# mote_cc3200v8.net
KiCad netlist of a schematic drawn in EAGLE
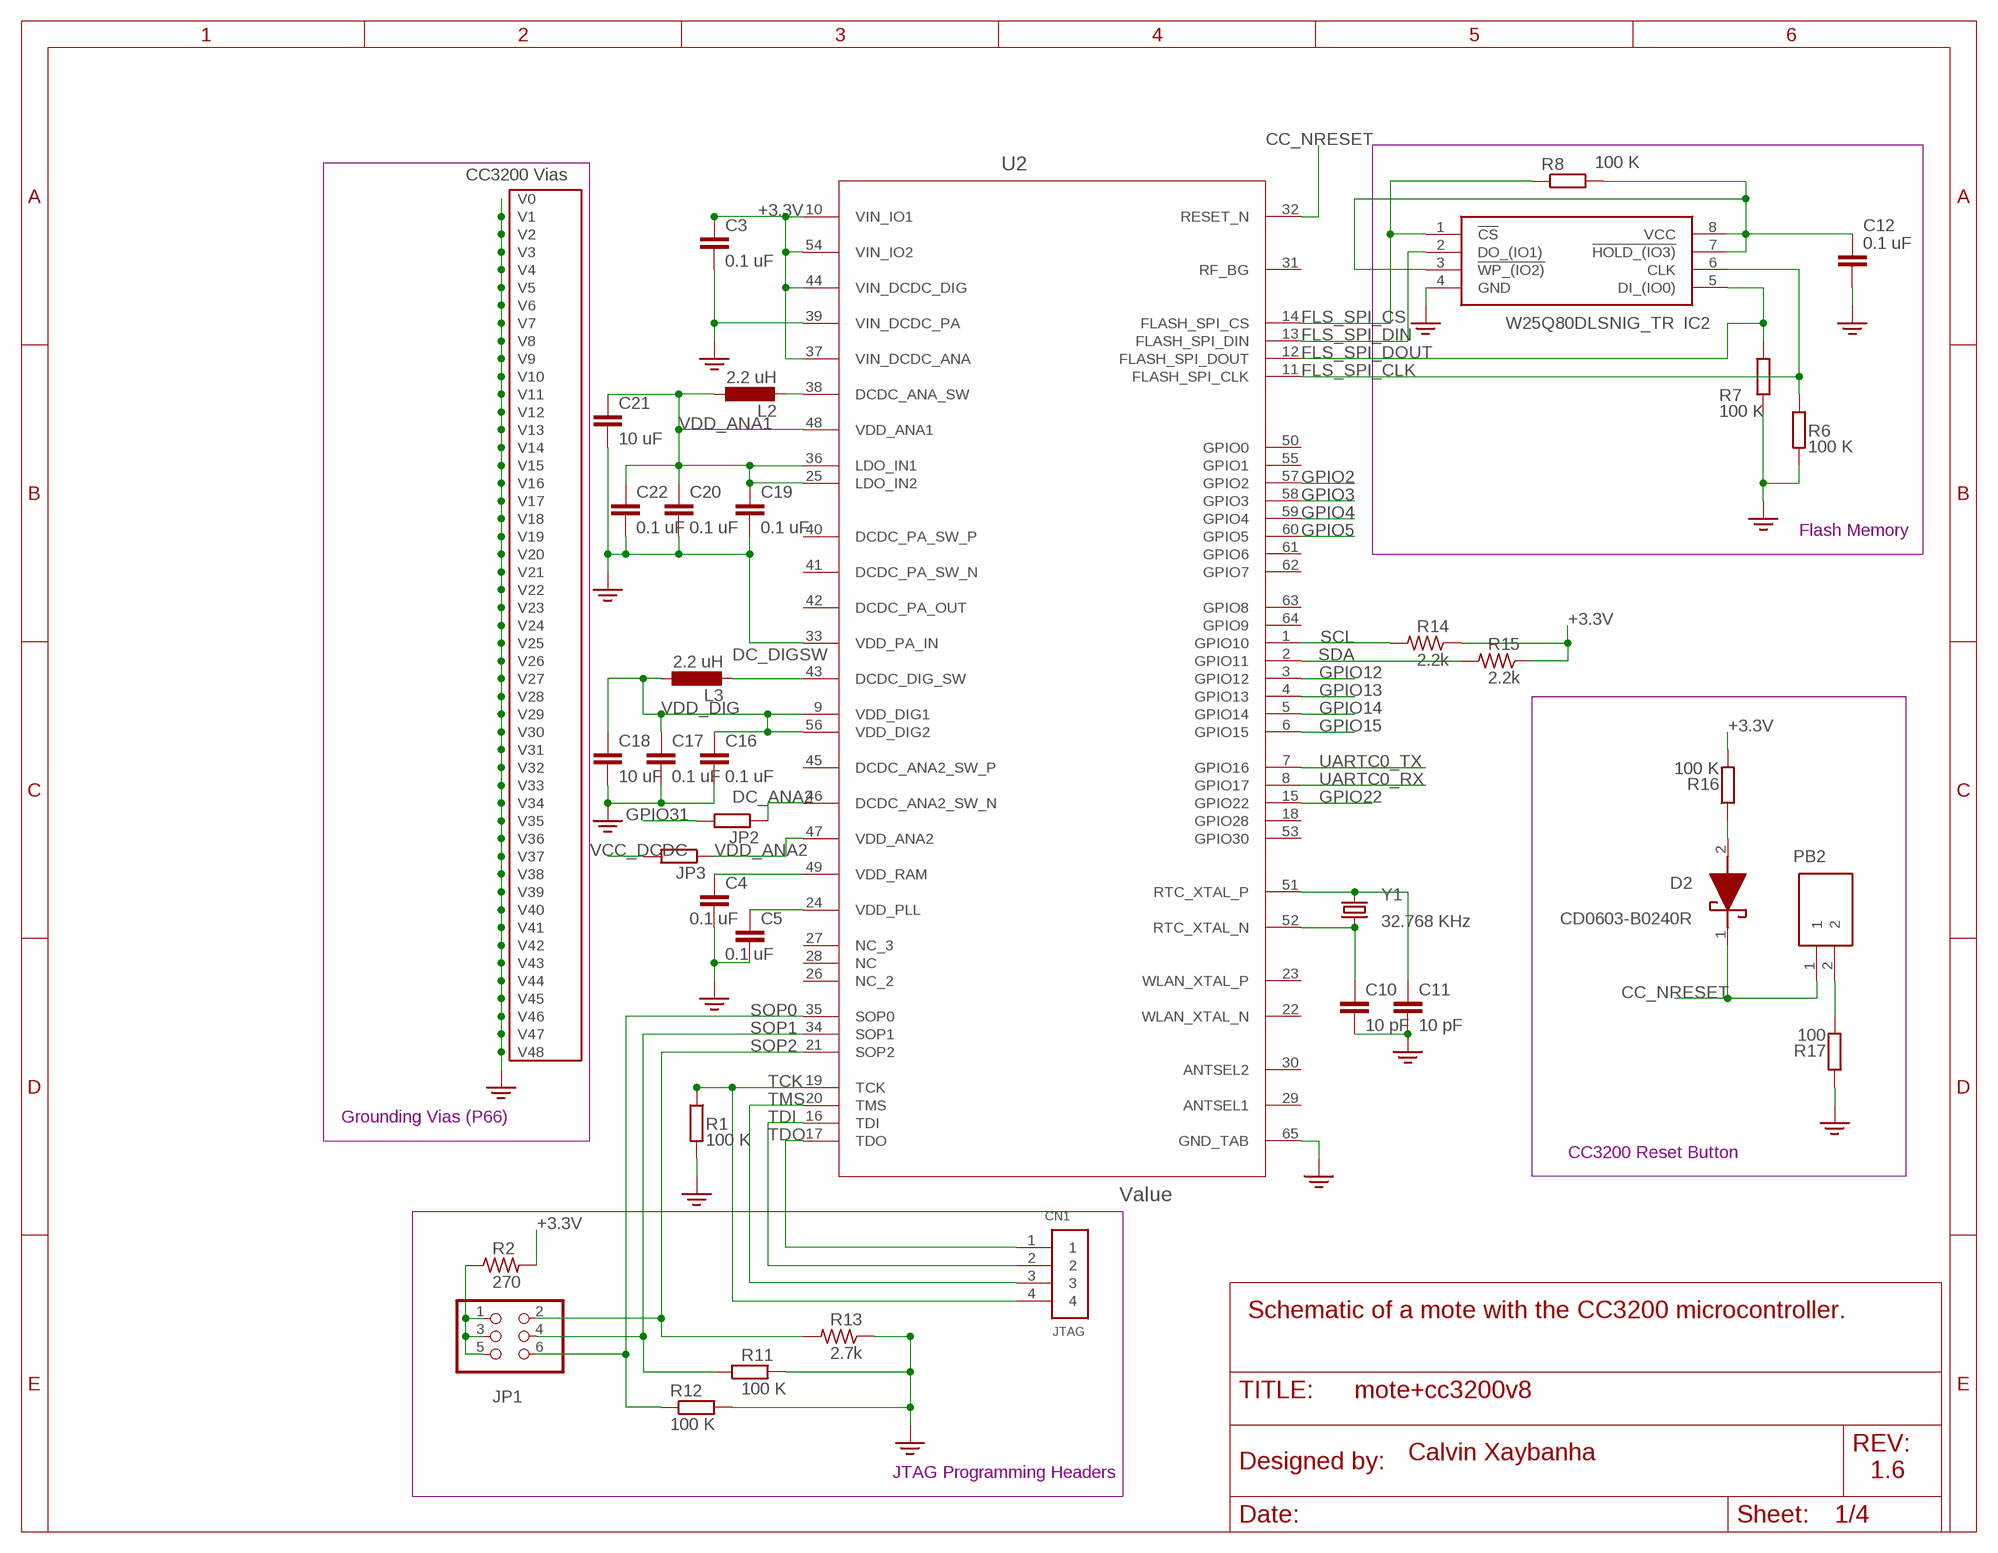
[diagram p0: schematic, sheet 1]
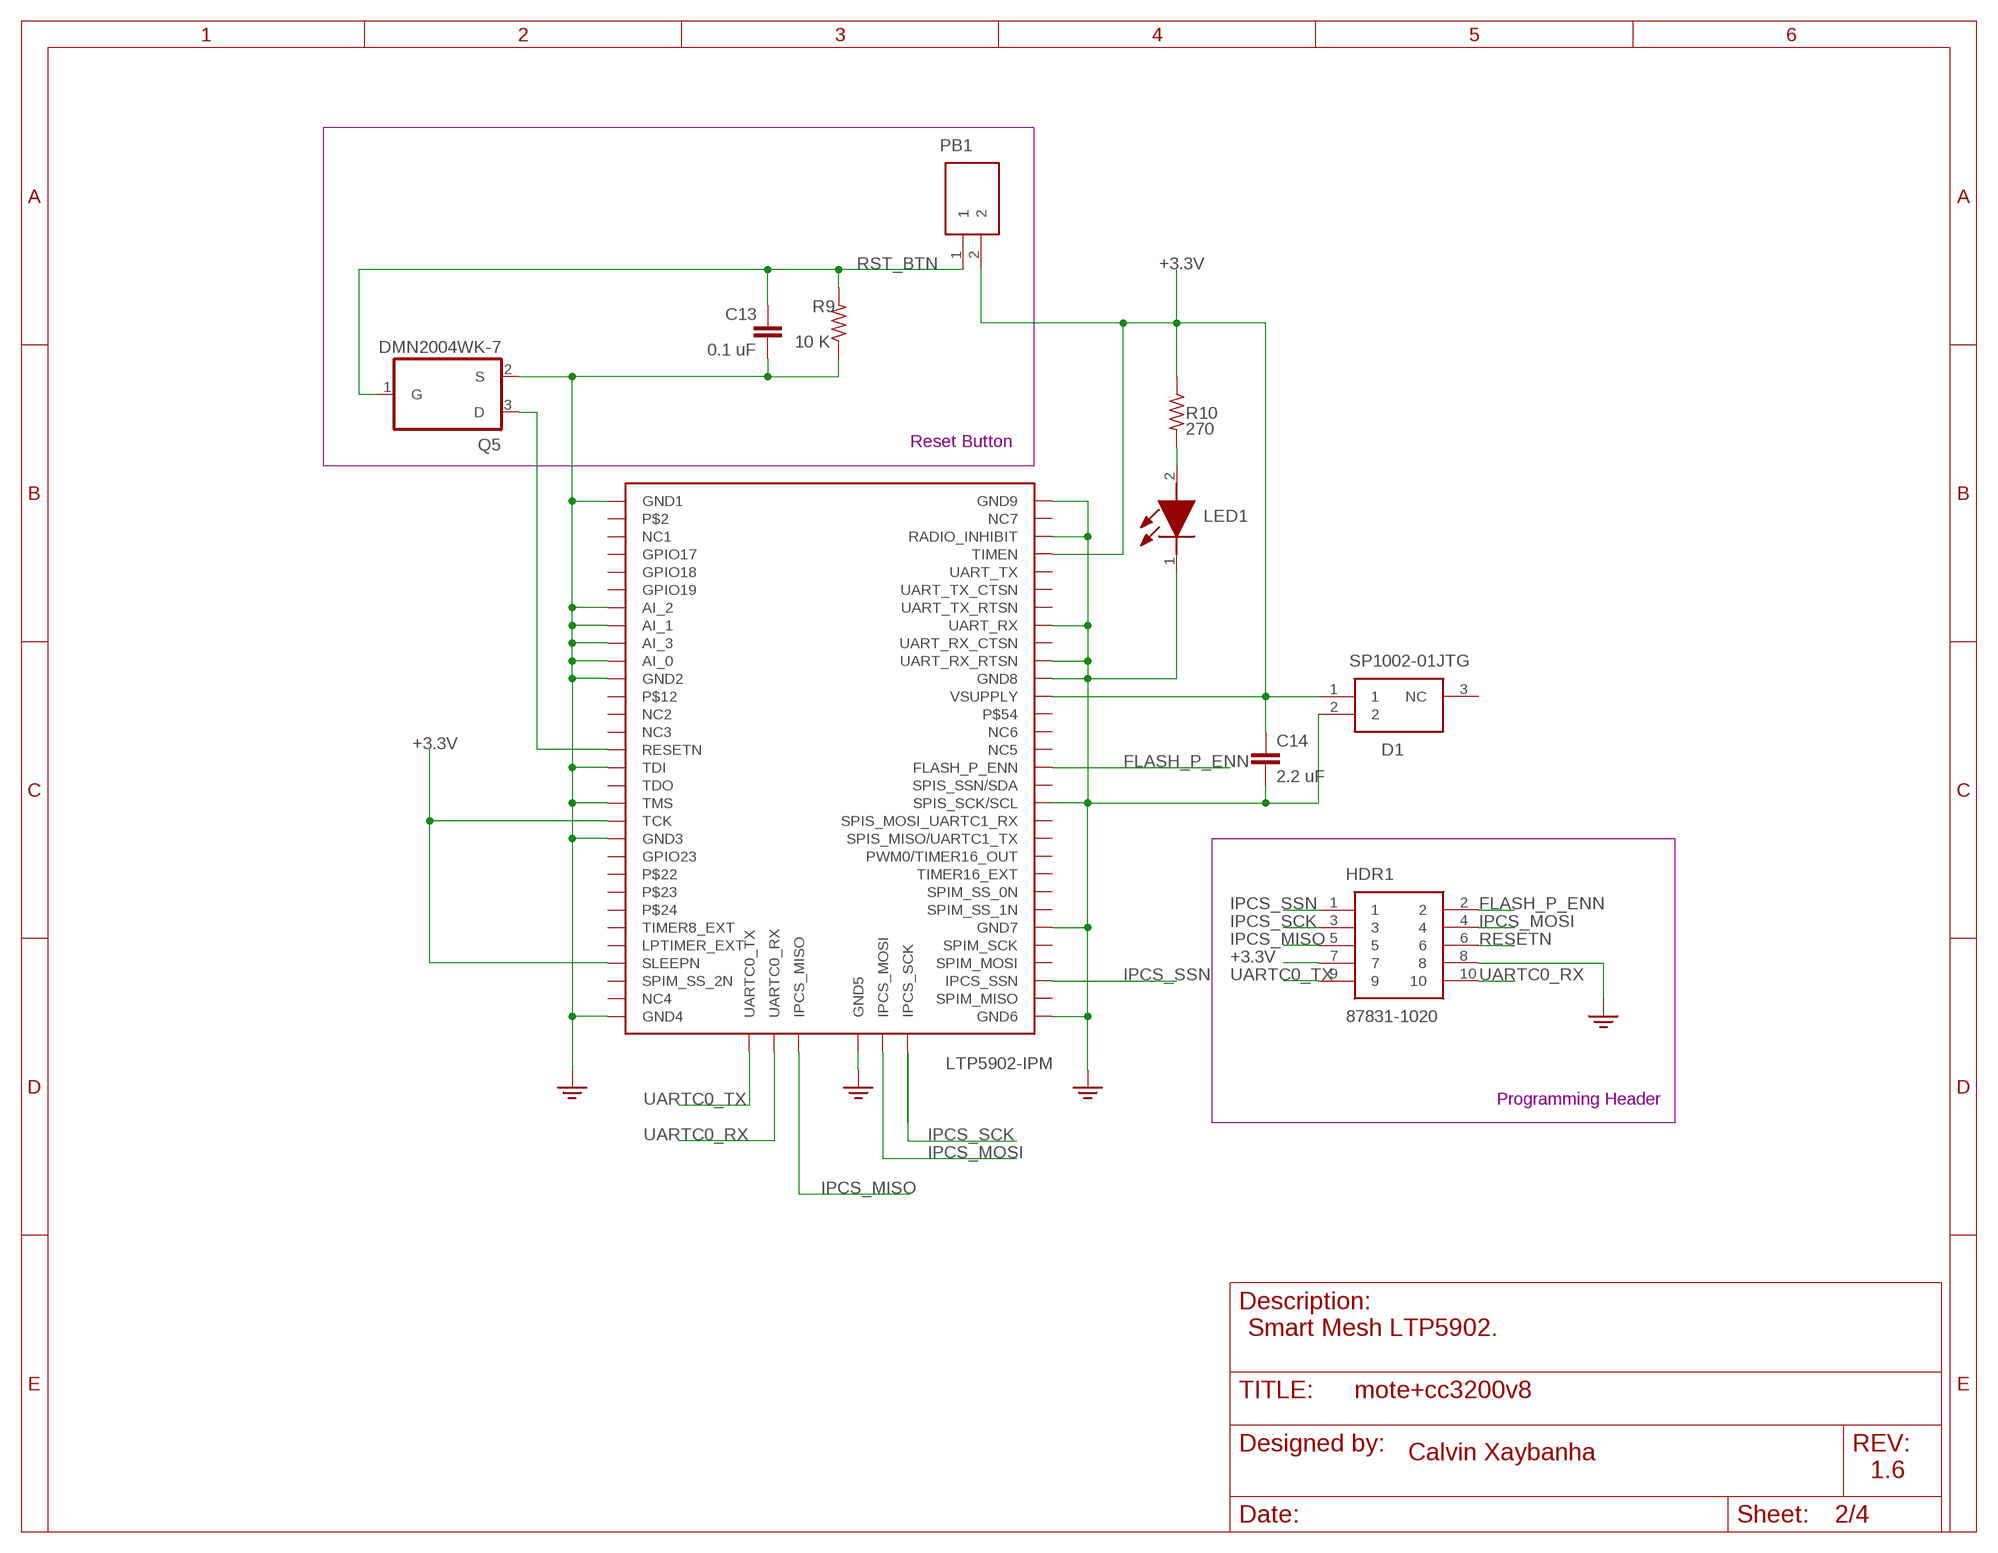
[diagram p1: schematic, sheet 2]
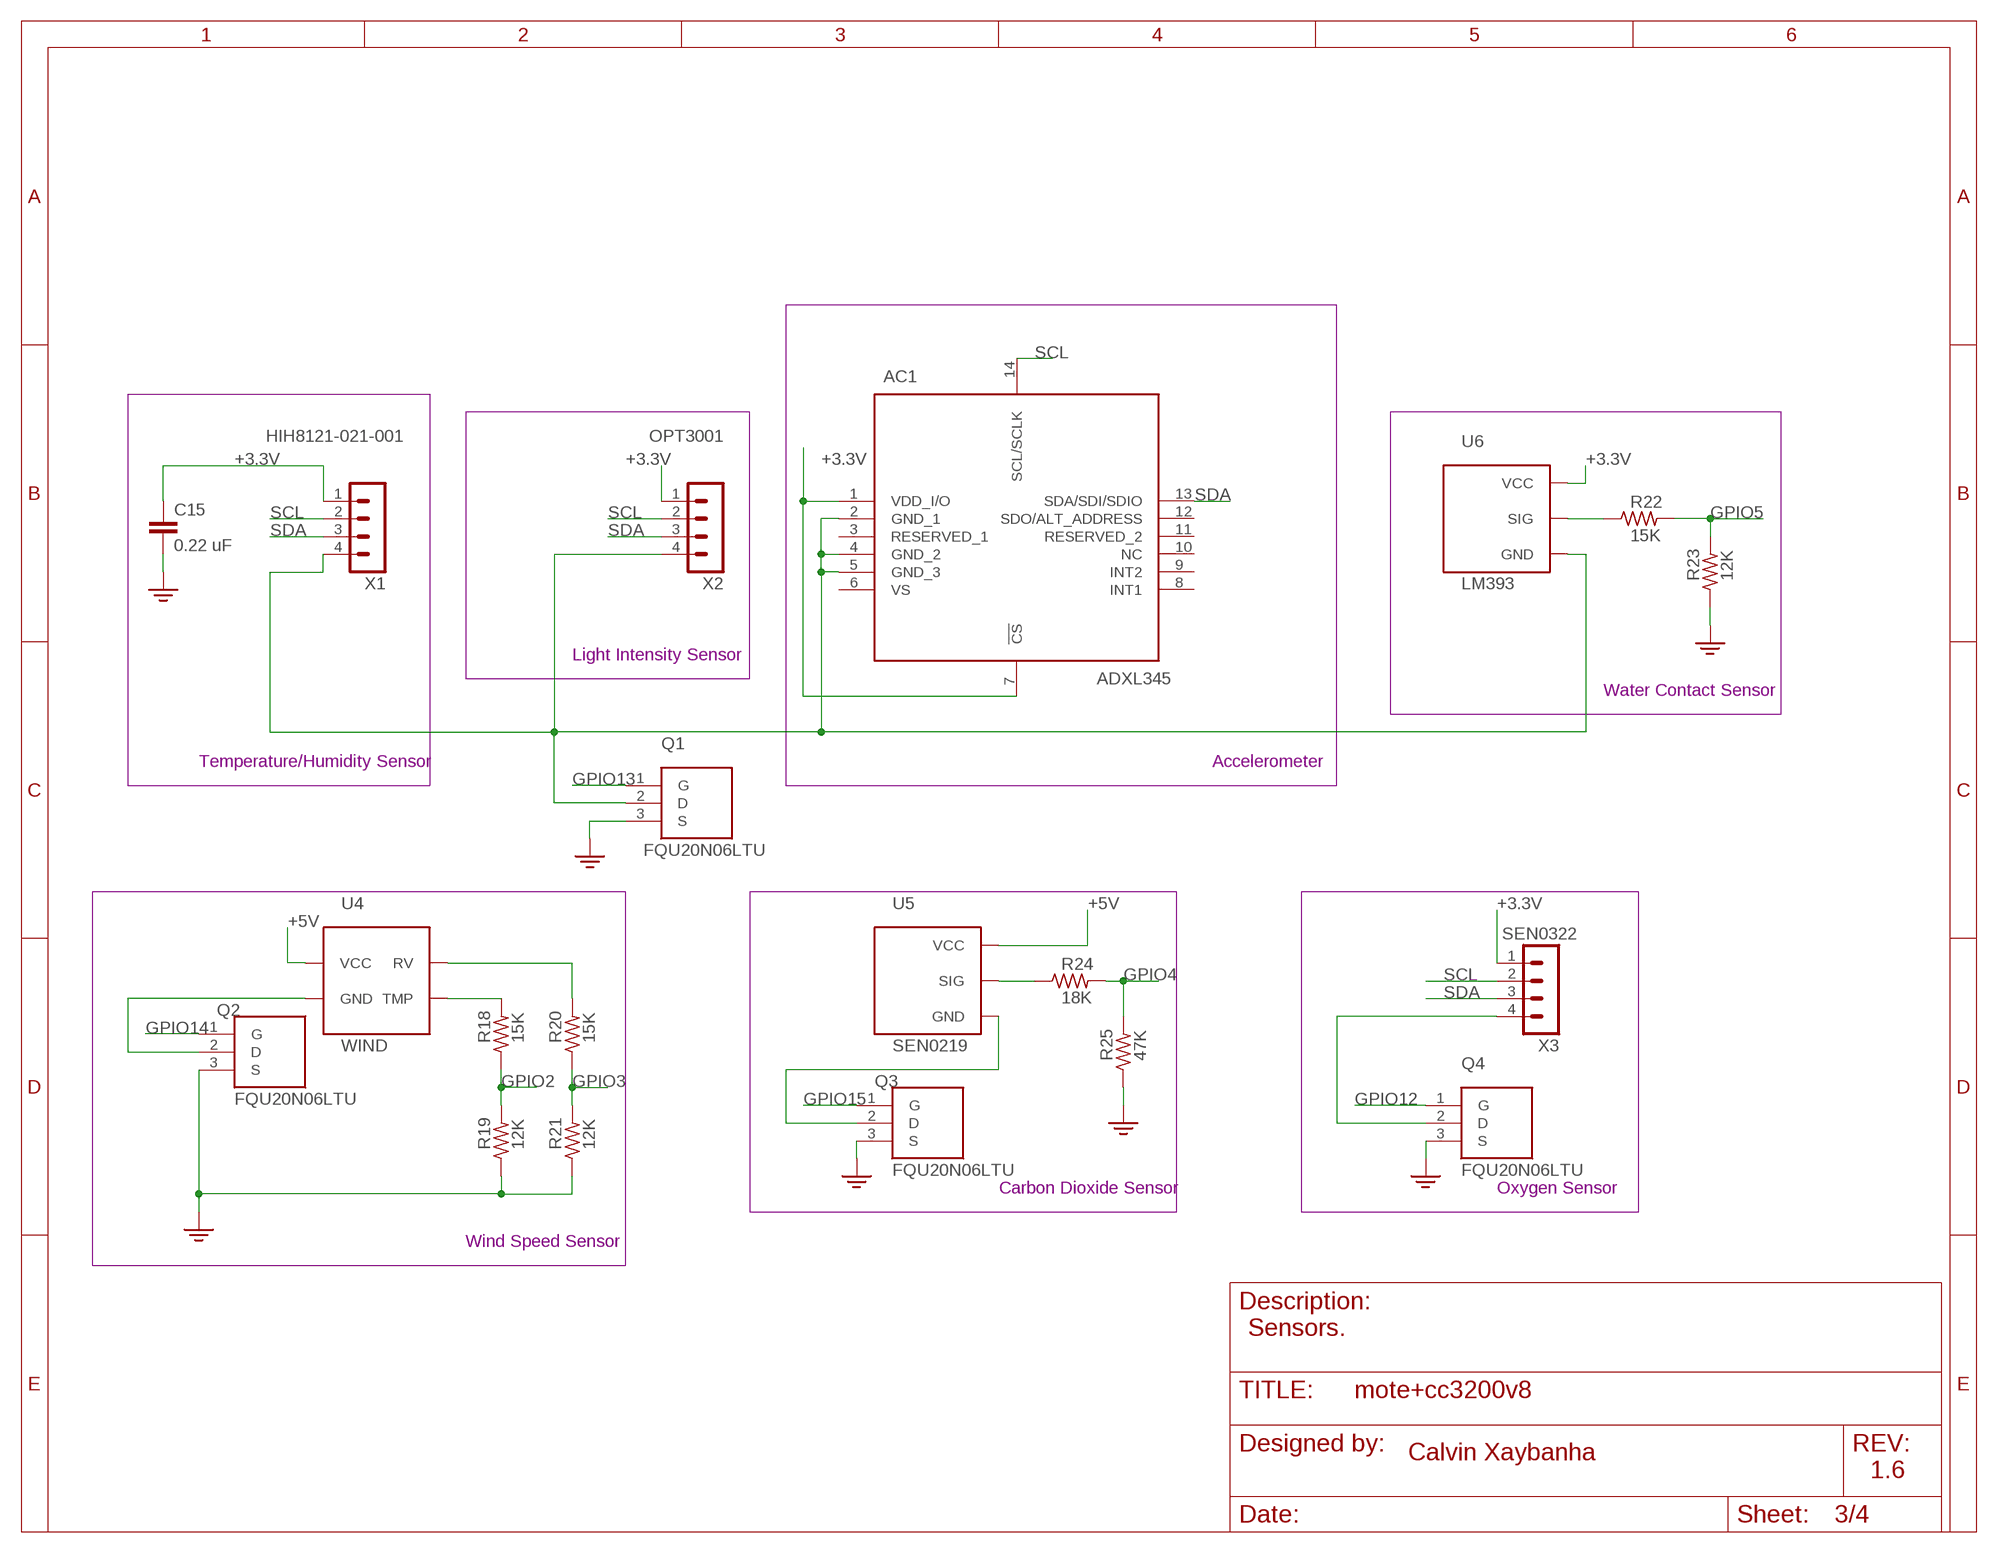
[diagram p2: schematic, sheet 3]
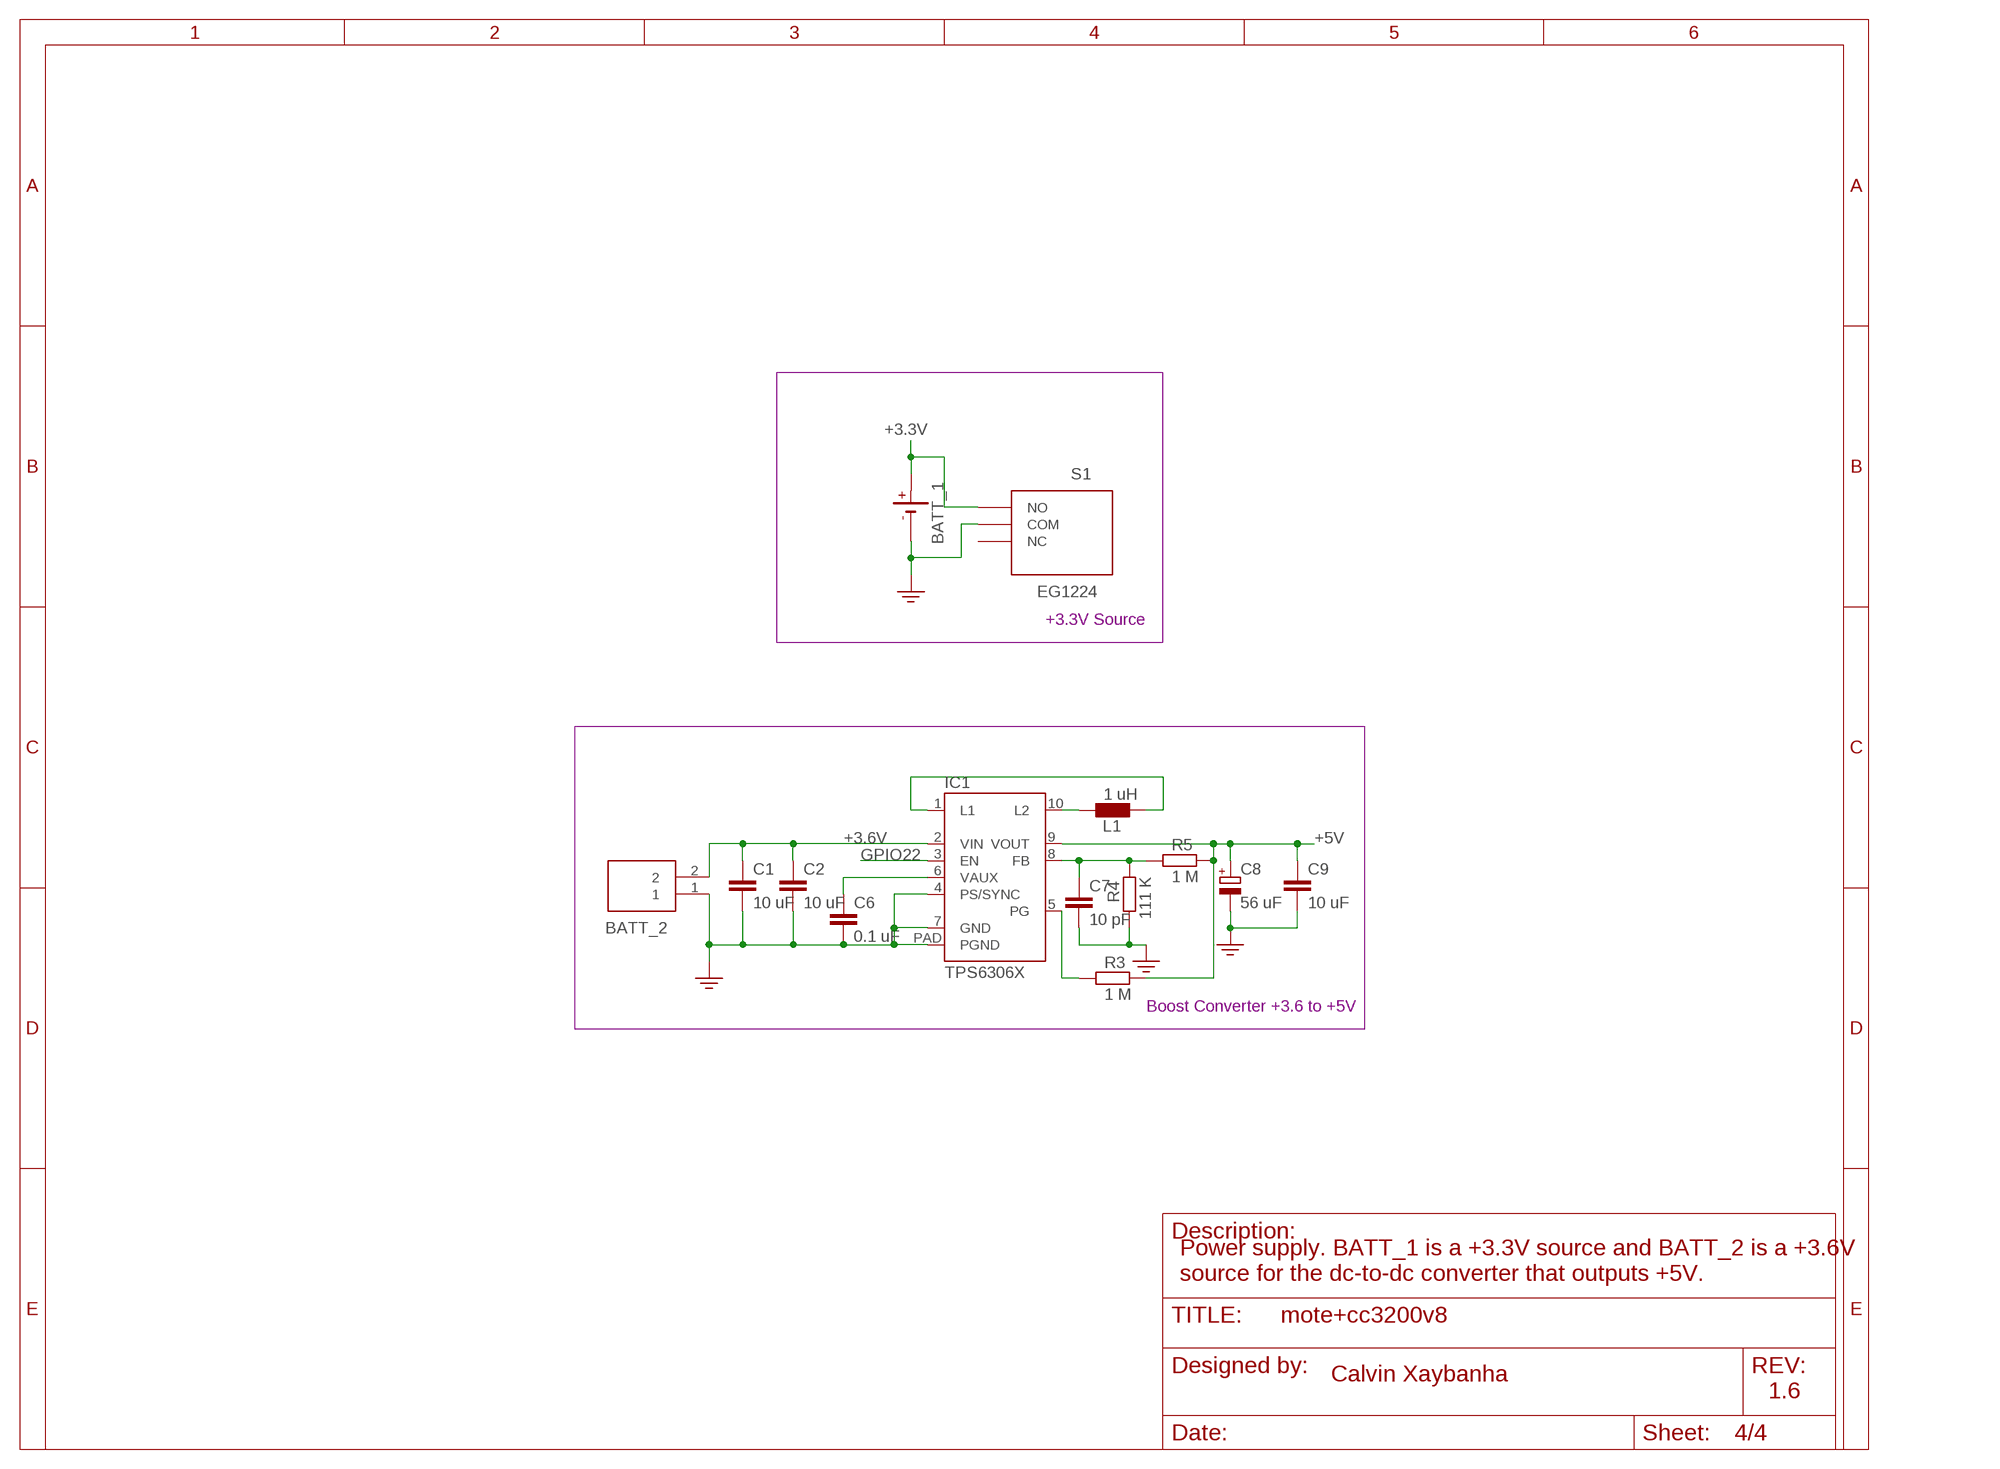
[diagram p3: schematic, sheet 4]

(export (version "E")
  (design (tool "Eeschema 10.0.6"))
  (components
    (comp (ref "BATT_1")
      (value "BATTERY_BR1225/FA")
      (footprint "eagle-import:BATTERY_BR1225_FA")
      (libsource (lib "eagle-import") (part "BATTERY_BR1225/FA"))
    )
    (comp (ref "BATT_2")
      (value "12BH23P-GR")
      (footprint "eagle-import:12BH23PGR")
      (libsource (lib "eagle-import") (part "12BH23P-GR"))
    )
    (comp (ref "C1")
      (value "10 uF")
      (footprint "eagle-import:C1808")
      (libsource (lib "eagle-import") (part "CC1808"))
    )
    (comp (ref "C2")
      (value "10 uF")
      (footprint "eagle-import:C1808")
      (libsource (lib "eagle-import") (part "CC1808"))
    )
    (comp (ref "C6")
      (value "0.1 uF")
      (footprint "eagle-import:C1808")
      (libsource (lib "eagle-import") (part "C-EUC1808"))
    )
    (comp (ref "C7")
      (value "10 pF")
      (footprint "eagle-import:C1808")
      (libsource (lib "eagle-import") (part "CC1808"))
    )
    (comp (ref "C8")
      (value "56 uF")
      (footprint "eagle-import:E3,5-8")
      (libsource (lib "eagle-import") (part "CPOL-EUE3.5-8"))
    )
    (comp (ref "C9")
      (value "10 uF")
      (footprint "eagle-import:C1808")
      (libsource (lib "eagle-import") (part "CC1808"))
    )
    (comp (ref "IC1")
      (value "TPS6306X")
      (footprint "eagle-import:S-PWSON-N10")
      (libsource (lib "eagle-import") (part "TPS6306X"))
    )
    (comp (ref "L1")
      (value "1 uH")
      (footprint "eagle-import:0204_7")
      (libsource (lib "eagle-import") (part "L0204/7"))
    )
    (comp (ref "R3")
      (value "1 M")
      (footprint "eagle-import:R5025")
      (libsource (lib "eagle-import") (part "R-EU_R5025"))
    )
    (comp (ref "R4")
      (value "111 K")
      (footprint "eagle-import:R1206")
      (libsource (lib "eagle-import") (part "R-EU_R1206"))
    )
    (comp (ref "R5")
      (value "1 M")
      (footprint "eagle-import:R5025")
      (libsource (lib "eagle-import") (part "R-EU_R5025"))
    )
    (comp (ref "S1")
      (value "EG1224")
      (footprint "eagle-import:EG1224")
      (fields (field (name "MOUSER_PART_NUMBER") "612-EG1224"))
      (libsource (lib "eagle-import") (part "EG1224"))
    )
    (comp (ref "C3")
      (value "0.1 uF")
      (footprint "eagle-import:C1808")
      (libsource (lib "eagle-import") (part "C-EUC1808"))
    )
    (comp (ref "C4")
      (value "0.1 uF")
      (footprint "eagle-import:C1808")
      (libsource (lib "eagle-import") (part "C-EUC1808"))
    )
    (comp (ref "C5")
      (value "0.1 uF")
      (footprint "eagle-import:C1808")
      (libsource (lib "eagle-import") (part "C-EUC1808"))
    )
    (comp (ref "C10")
      (value "10 pF")
      (footprint "eagle-import:C1808")
      (libsource (lib "eagle-import") (part "CC1808"))
    )
    (comp (ref "C11")
      (value "10 pF")
      (footprint "eagle-import:C1808")
      (libsource (lib "eagle-import") (part "CC1808"))
    )
    (comp (ref "C12")
      (value "0.1 uF")
      (footprint "eagle-import:C1808")
      (libsource (lib "eagle-import") (part "C-EUC1808"))
    )
    (comp (ref "C16")
      (value "0.1 uF")
      (footprint "eagle-import:C1808")
      (libsource (lib "eagle-import") (part "C-EUC1808"))
    )
    (comp (ref "C17")
      (value "0.1 uF")
      (footprint "eagle-import:C1808")
      (libsource (lib "eagle-import") (part "C-EUC1808"))
    )
    (comp (ref "C18")
      (value "10 uF")
      (footprint "eagle-import:C1808")
      (libsource (lib "eagle-import") (part "CC1808"))
    )
    (comp (ref "C19")
      (value "0.1 uF")
      (footprint "eagle-import:C1808")
      (libsource (lib "eagle-import") (part "C-EUC1808"))
    )
    (comp (ref "C20")
      (value "0.1 uF")
      (footprint "eagle-import:C1808")
      (libsource (lib "eagle-import") (part "C-EUC1808"))
    )
    (comp (ref "C21")
      (value "10 uF")
      (footprint "eagle-import:C1808")
      (libsource (lib "eagle-import") (part "CC1808"))
    )
    (comp (ref "C22")
      (value "0.1 uF")
      (footprint "eagle-import:C1808")
      (libsource (lib "eagle-import") (part "C-EUC1808"))
    )
    (comp (ref "CN1")
      (value "JTAG")
      (footprint "eagle-import:1X04-BIG")
      (libsource (lib "eagle-import") (part "1X4-BIG"))
    )
    (comp (ref "D2")
      (value "CD0603-B0240R")
      (footprint "eagle-import:CD0603B0240R")
      (fields (field (name "MOUSER_PART_NUMBER") "652-CD0603-B0240R"))
      (libsource (lib "eagle-import") (part "CD0603-B0240R"))
    )
    (comp (ref "IC2")
      (value "W25Q80DLSNIG_TR")
      (footprint "eagle-import:SOIC127P600X175-8N")
      (fields
        (field (name "MANUFACTURER_PART_NUMBER") "W25Q80DLSNIG TR")
        (field (name "MOUSER_PART_NUMBER") "454-W25Q80DLSNIGTR")
      )
      (libsource (lib "eagle-import") (part "W25Q80DLSNIG_TR"))
    )
    (comp (ref "JP1")
      (value "PINHD-2X3/90")
      (footprint "eagle-import:2X03_90")
      (libsource (lib "eagle-import") (part "PINHD-2X3/90"))
    )
    (comp (ref "JP2")
      (value "RR0201")
      (footprint "eagle-import:R0201")
      (libsource (lib "eagle-import") (part "RR0201"))
    )
    (comp (ref "JP3")
      (value "RR0201")
      (footprint "eagle-import:R0201")
      (libsource (lib "eagle-import") (part "RR0201"))
    )
    (comp (ref "L2")
      (value "2.2 uH")
      (footprint "eagle-import:L3216C")
      (libsource (lib "eagle-import") (part "L-EUL3216C"))
    )
    (comp (ref "L3")
      (value "2.2 uH")
      (footprint "eagle-import:L3216C")
      (libsource (lib "eagle-import") (part "L-EUL3216C"))
    )
    (comp (ref "PB2")
      (value "FSMSM")
      (footprint "eagle-import:FSMSM")
      (fields (field (name "MOUSER_PART_NUMBER") "506-FSMSM"))
      (libsource (lib "eagle-import") (part "FSMSM"))
    )
    (comp (ref "R1")
      (value "100 K")
      (footprint "eagle-import:R1206")
      (libsource (lib "eagle-import") (part "R-EU_R1206"))
    )
    (comp (ref "R2")
      (value "270")
      (footprint "eagle-import:RES_1206")
      (fields
        (field (name "DIGIKEY_PART_NUMBER") "WSLP-.05TR-ND")
        (field (name "MANUFACTURER") "Vishay Dale")
        (field (name "MPN") "WSLP1206R0500FEA")
        (field (name "CREATED_BY") "PCBLayout.com")
      )
      (libsource (lib "eagle-import") (part "WSLP1206R0500FEA"))
    )
    (comp (ref "R6")
      (value "100 K")
      (footprint "eagle-import:R1206")
      (libsource (lib "eagle-import") (part "R-EU_R1206"))
    )
    (comp (ref "R7")
      (value "100 K")
      (footprint "eagle-import:R1206")
      (libsource (lib "eagle-import") (part "R-EU_R1206"))
    )
    (comp (ref "R8")
      (value "100 K")
      (footprint "eagle-import:R1206")
      (libsource (lib "eagle-import") (part "R-EU_R1206"))
    )
    (comp (ref "R11")
      (value "100 K")
      (footprint "eagle-import:R1206")
      (libsource (lib "eagle-import") (part "R-EU_R1206"))
    )
    (comp (ref "R12")
      (value "100 K")
      (footprint "eagle-import:R1206")
      (libsource (lib "eagle-import") (part "R-EU_R1206"))
    )
    (comp (ref "R13")
      (value "2.7k")
      (footprint "eagle-import:RES_1206")
      (fields
        (field (name "DIGIKEY_PART_NUMBER") "WSLP-.05TR-ND")
        (field (name "MANUFACTURER") "Vishay Dale")
        (field (name "MPN") "WSLP1206R0500FEA")
        (field (name "CREATED_BY") "PCBLayout.com")
      )
      (libsource (lib "eagle-import") (part "WSLP1206R0500FEA"))
    )
    (comp (ref "R14")
      (value "2.2k")
      (footprint "eagle-import:RES_1206")
      (fields
        (field (name "DIGIKEY_PART_NUMBER") "WSLP-.05TR-ND")
        (field (name "MANUFACTURER") "Vishay Dale")
        (field (name "MPN") "WSLP1206R0500FEA")
        (field (name "CREATED_BY") "PCBLayout.com")
      )
      (libsource (lib "eagle-import") (part "WSLP1206R0500FEA"))
    )
    (comp (ref "R15")
      (value "2.2k")
      (footprint "eagle-import:RES_1206")
      (fields
        (field (name "DIGIKEY_PART_NUMBER") "WSLP-.05TR-ND")
        (field (name "MANUFACTURER") "Vishay Dale")
        (field (name "MPN") "WSLP1206R0500FEA")
        (field (name "CREATED_BY") "PCBLayout.com")
      )
      (libsource (lib "eagle-import") (part "WSLP1206R0500FEA"))
    )
    (comp (ref "R16")
      (value "100 K")
      (footprint "eagle-import:R1206")
      (libsource (lib "eagle-import") (part "R-EU_R1206"))
    )
    (comp (ref "R17")
      (value "100")
      (footprint "eagle-import:R1206")
      (libsource (lib "eagle-import") (part "R-EU_R1206"))
    )
    (comp (ref "U2")
      (value "Value")
      (footprint "eagle-import:RGC0064A")
      (fields
        (field (name "ALTERNATEPARTNUMBER") "CC3200R1M2RGC")
        (field (name "MANUFACTURER") "Texas Instruments")
        (field (name "PARTNUMBER") "CC3200R1M2RGCR")
      )
      (libsource (lib "eagle-import") (part "CC3200R1M2RGCR"))
    )
    (comp (ref "Y1")
      (value "32.768 KHz")
      (footprint "eagle-import:7.0X5.0")
      (libsource (lib "eagle-import") (part "KX-13"))
    )
    (comp (ref "C13")
      (value "0.1 uF")
      (footprint "eagle-import:C1808")
      (libsource (lib "eagle-import") (part "C-EUC1808"))
    )
    (comp (ref "C14")
      (value "2.2 uF")
      (footprint "eagle-import:C1808")
      (libsource (lib "eagle-import") (part "CC1808"))
    )
    (comp (ref "D1")
      (value "SP1002-01JTG")
      (footprint "eagle-import:SOT132P220X110-3N")
      (fields (field (name "MOUSER_PART_NUMBER") "576-SP1002-01JTG"))
      (libsource (lib "eagle-import") (part "SP1002-01JTG"))
    )
    (comp (ref "HDR1")
      (value "87831-1020")
      (footprint "eagle-import:SHDR10W55P200_2X5_1265X630X640")
      (fields (field (name "MOUSER_PART_NUMBER") "538-87831-1020"))
      (libsource (lib "eagle-import") (part "87831-1020"))
    )
    (comp (ref "LED1")
      (value "156120RS75000")
      (footprint "eagle-import:LEDM3216X130N")
      (fields (field (name "MOUSER_PART_NUMBER") "710-156120RS75000"))
      (libsource (lib "eagle-import") (part "156120RS75000"))
    )
    (comp (ref "PB1")
      (value "FSMSM")
      (footprint "eagle-import:FSMSM")
      (fields (field (name "MOUSER_PART_NUMBER") "506-FSMSM"))
      (libsource (lib "eagle-import") (part "FSMSM"))
    )
    (comp (ref "Q5")
      (value "DMN2004WK-7")
      (footprint "eagle-import:SC70-3_DCK")
      (libsource (lib "eagle-import") (part "DMN2004WK-7"))
    )
    (comp (ref "R9")
      (value "10 K")
      (footprint "eagle-import:RES_1206")
      (fields
        (field (name "DIGIKEY_PART_NUMBER") "WSLP-.05TR-ND")
        (field (name "MANUFACTURER") "Vishay Dale")
        (field (name "MPN") "WSLP1206R0500FEA")
        (field (name "CREATED_BY") "PCBLayout.com")
      )
      (libsource (lib "eagle-import") (part "WSLP1206R0500FEA"))
    )
    (comp (ref "R10")
      (value "270")
      (footprint "eagle-import:RES_1206")
      (fields
        (field (name "DIGIKEY_PART_NUMBER") "WSLP-.05TR-ND")
        (field (name "MANUFACTURER") "Vishay Dale")
        (field (name "MPN") "WSLP1206R0500FEA")
        (field (name "CREATED_BY") "PCBLayout.com")
      )
      (libsource (lib "eagle-import") (part "WSLP1206R0500FEA"))
    )
    (comp (ref "U3")
      (value "LTP5902")
      (footprint "eagle-import:LTP5902-MMCX")
      (libsource (lib "eagle-import") (part "LTP5902"))
    )
    (comp (ref "AC1")
      (value "ADXL345")
      (footprint "eagle-import:CC-14-1")
      (libsource (lib "eagle-import") (part "ADXL345"))
    )
    (comp (ref "C15")
      (value "0.22 uF")
      (footprint "eagle-import:C1808")
      (libsource (lib "eagle-import") (part "C-EUC1808"))
    )
    (comp (ref "Q1")
      (value "FQU20N06LTU")
      (footprint "eagle-import:TO229P250X658X985-3P")
      (fields (field (name "MOUSER_PART_NUMBER") "512-FQU20N06LTU"))
      (libsource (lib "eagle-import") (part "FQU20N06LTU"))
    )
    (comp (ref "Q2")
      (value "FQU20N06LTU")
      (footprint "eagle-import:TO229P250X658X985-3P")
      (fields (field (name "MOUSER_PART_NUMBER") "512-FQU20N06LTU"))
      (libsource (lib "eagle-import") (part "FQU20N06LTU"))
    )
    (comp (ref "Q3")
      (value "FQU20N06LTU")
      (footprint "eagle-import:TO229P250X658X985-3P")
      (fields (field (name "MOUSER_PART_NUMBER") "512-FQU20N06LTU"))
      (libsource (lib "eagle-import") (part "FQU20N06LTU"))
    )
    (comp (ref "Q4")
      (value "FQU20N06LTU")
      (footprint "eagle-import:TO229P250X658X985-3P")
      (fields (field (name "MOUSER_PART_NUMBER") "512-FQU20N06LTU"))
      (libsource (lib "eagle-import") (part "FQU20N06LTU"))
    )
    (comp (ref "R18")
      (value "15K")
      (footprint "eagle-import:RES_1206")
      (fields
        (field (name "DIGIKEY_PART_NUMBER") "WSLP-.05TR-ND")
        (field (name "MANUFACTURER") "Vishay Dale")
        (field (name "MPN") "WSLP1206R0500FEA")
        (field (name "CREATED_BY") "PCBLayout.com")
      )
      (libsource (lib "eagle-import") (part "WSLP1206R0500FEA"))
    )
    (comp (ref "R19")
      (value "12K")
      (footprint "eagle-import:RES_1206")
      (fields
        (field (name "DIGIKEY_PART_NUMBER") "WSLP-.05TR-ND")
        (field (name "MANUFACTURER") "Vishay Dale")
        (field (name "MPN") "WSLP1206R0500FEA")
        (field (name "CREATED_BY") "PCBLayout.com")
      )
      (libsource (lib "eagle-import") (part "WSLP1206R0500FEA"))
    )
    (comp (ref "R20")
      (value "15K")
      (footprint "eagle-import:RES_1206")
      (fields
        (field (name "DIGIKEY_PART_NUMBER") "WSLP-.05TR-ND")
        (field (name "MANUFACTURER") "Vishay Dale")
        (field (name "MPN") "WSLP1206R0500FEA")
        (field (name "CREATED_BY") "PCBLayout.com")
      )
      (libsource (lib "eagle-import") (part "WSLP1206R0500FEA"))
    )
    (comp (ref "R21")
      (value "12K")
      (footprint "eagle-import:RES_1206")
      (fields
        (field (name "DIGIKEY_PART_NUMBER") "WSLP-.05TR-ND")
        (field (name "MANUFACTURER") "Vishay Dale")
        (field (name "MPN") "WSLP1206R0500FEA")
        (field (name "CREATED_BY") "PCBLayout.com")
      )
      (libsource (lib "eagle-import") (part "WSLP1206R0500FEA"))
    )
    (comp (ref "R22")
      (value "15K")
      (footprint "eagle-import:RES_1206")
      (fields
        (field (name "DIGIKEY_PART_NUMBER") "WSLP-.05TR-ND")
        (field (name "MANUFACTURER") "Vishay Dale")
        (field (name "MPN") "WSLP1206R0500FEA")
        (field (name "CREATED_BY") "PCBLayout.com")
      )
      (libsource (lib "eagle-import") (part "WSLP1206R0500FEA"))
    )
    (comp (ref "R23")
      (value "12K")
      (footprint "eagle-import:RES_1206")
      (fields
        (field (name "DIGIKEY_PART_NUMBER") "WSLP-.05TR-ND")
        (field (name "MANUFACTURER") "Vishay Dale")
        (field (name "MPN") "WSLP1206R0500FEA")
        (field (name "CREATED_BY") "PCBLayout.com")
      )
      (libsource (lib "eagle-import") (part "WSLP1206R0500FEA"))
    )
    (comp (ref "R24")
      (value "18K")
      (footprint "eagle-import:RES_1206")
      (fields
        (field (name "DIGIKEY_PART_NUMBER") "WSLP-.05TR-ND")
        (field (name "MANUFACTURER") "Vishay Dale")
        (field (name "MPN") "WSLP1206R0500FEA")
        (field (name "CREATED_BY") "PCBLayout.com")
      )
      (libsource (lib "eagle-import") (part "WSLP1206R0500FEA"))
    )
    (comp (ref "R25")
      (value "47K")
      (footprint "eagle-import:RES_1206")
      (fields
        (field (name "DIGIKEY_PART_NUMBER") "WSLP-.05TR-ND")
        (field (name "MANUFACTURER") "Vishay Dale")
        (field (name "MPN") "WSLP1206R0500FEA")
        (field (name "CREATED_BY") "PCBLayout.com")
      )
      (libsource (lib "eagle-import") (part "WSLP1206R0500FEA"))
    )
    (comp (ref "U4")
      (value "WIND")
      (footprint "eagle-import:WIND")
      (libsource (lib "eagle-import") (part "WIND"))
    )
    (comp (ref "U5")
      (value "SEN0219")
      (footprint "eagle-import:SEN0219")
      (libsource (lib "eagle-import") (part "SEN0219"))
    )
    (comp (ref "U6")
      (value "LM393")
      (footprint "eagle-import:LM393")
      (libsource (lib "eagle-import") (part "LM393"))
    )
    (comp (ref "X1")
      (value "HIH8121-021-001")
      (footprint "eagle-import:B4B-PH-K-S")
      (libsource (lib "eagle-import") (part "B4B-PH-K-S"))
    )
    (comp (ref "X2")
      (value "OPT3001")
      (footprint "eagle-import:B4B-PH-K-S")
      (libsource (lib "eagle-import") (part "B4B-PH-K-S"))
    )
    (comp (ref "X3")
      (value "SEN0322")
      (footprint "eagle-import:B4B-PH-K-S")
      (libsource (lib "eagle-import") (part "B4B-PH-K-S"))
    )
  )
  (nets
    (net (code "1") (name "+3.3V") (class "Default")
      (node (ref "AC1") (pin "1") (pinfunction "VDD_I/O_1") (pintype "power_in"))
      (node (ref "AC1") (pin "7") (pinfunction "~{CS}_7") (pintype "input"))
      (node (ref "BATT_1") (pin "+") (pinfunction "+_+") (pintype "passive"))
      (node (ref "C12") (pin "1") (pinfunction "1_1") (pintype "passive"))
      (node (ref "C14") (pin "1") (pinfunction "1_1") (pintype "passive"))
      (node (ref "C15") (pin "1") (pinfunction "1_1") (pintype "passive"))
      (node (ref "C3") (pin "1") (pinfunction "1_1") (pintype "passive"))
      (node (ref "D1") (pin "1") (pinfunction "1_1") (pintype "bidirectional"))
      (node (ref "HDR1") (pin "7") (pinfunction "7_7") (pintype "bidirectional"))
      (node (ref "IC2") (pin "3") (pinfunction "~{WP_(IO2})_3") (pintype "bidirectional"))
      (node (ref "IC2") (pin "7") (pinfunction "~{HOLD_(IO3})_7") (pintype "bidirectional"))
      (node (ref "IC2") (pin "8") (pinfunction "VCC_8") (pintype "bidirectional"))
      (node (ref "PB1") (pin "2") (pinfunction "2_2") (pintype "bidirectional"))
      (node (ref "R10") (pin "1") (pinfunction "1_1") (pintype "passive"))
      (node (ref "R14") (pin "1") (pinfunction "1_1") (pintype "passive"))
      (node (ref "R15") (pin "1") (pinfunction "1_1") (pintype "passive"))
      (node (ref "R16") (pin "2") (pinfunction "2_2") (pintype "passive"))
      (node (ref "R2") (pin "2") (pinfunction "2_2") (pintype "passive"))
      (node (ref "R8") (pin "2") (pinfunction "2_2") (pintype "passive"))
      (node (ref "S1") (pin "1") (pinfunction "NO_1") (pintype "bidirectional"))
      (node (ref "U2") (pin "10") (pinfunction "VIN_IO1_10") (pintype "power_in"))
      (node (ref "U2") (pin "37") (pinfunction "VIN_DCDC_ANA_37") (pintype "power_in"))
      (node (ref "U2") (pin "44") (pinfunction "VIN_DCDC_DIG_44") (pintype "power_in"))
      (node (ref "U2") (pin "54") (pinfunction "VIN_IO2_54") (pintype "power_in"))
      (node (ref "U3") (pin "P19") (pinfunction "TCK_P19") (pintype "bidirectional"))
      (node (ref "U3") (pin "P27") (pinfunction "SLEEPN_P27") (pintype "bidirectional"))
      (node (ref "U3") (pin "P55") (pinfunction "VSUPPLY_P55") (pintype "bidirectional"))
      (node (ref "U3") (pin "P63") (pinfunction "TIMEN_P63") (pintype "bidirectional"))
      (node (ref "U6") (pin "P$1") (pinfunction "VCC_P$1") (pintype "power_in"))
      (node (ref "X1") (pin "1") (pinfunction "1_1") (pintype "power_in"))
      (node (ref "X2") (pin "1") (pinfunction "1_1") (pintype "power_in"))
      (node (ref "X3") (pin "1") (pinfunction "1_1") (pintype "power_in"))
    )
    (net (code "2") (name "+3.6V") (class "Default")
      (node (ref "BATT_2") (pin "2") (pinfunction "2_2") (pintype "bidirectional"))
      (node (ref "C1") (pin "1") (pinfunction "1_1") (pintype "passive"))
      (node (ref "C2") (pin "1") (pinfunction "1_1") (pintype "passive"))
      (node (ref "IC1") (pin "2") (pinfunction "VIN_2") (pintype "passive"))
    )
    (net (code "3") (name "+5V") (class "Default")
      (node (ref "C8") (pin "+") (pinfunction "+_+") (pintype "passive"))
      (node (ref "C9") (pin "1") (pinfunction "1_1") (pintype "passive"))
      (node (ref "IC1") (pin "9") (pinfunction "VOUT_9") (pintype "passive"))
      (node (ref "R3") (pin "2") (pinfunction "2_2") (pintype "passive"))
      (node (ref "R5") (pin "2") (pinfunction "2_2") (pintype "passive"))
      (node (ref "U4") (pin "P$1") (pinfunction "VCC_P$1") (pintype "power_in"))
      (node (ref "U5") (pin "P$1") (pinfunction "VCC_P$1") (pintype "power_in"))
    )
    (net (code "4") (name "CC_NRESET") (class "Default")
      (node (ref "D2") (pin "1") (pinfunction "K_1") (pintype "bidirectional"))
      (node (ref "PB2") (pin "1") (pinfunction "1_1") (pintype "bidirectional"))
      (node (ref "U2") (pin "32") (pinfunction "RESET_N_32") (pintype "input"))
    )
    (net (code "5") (name "DCDC_PA_OUT") (class "Default")
      (node (ref "U2") (pin "42") (pinfunction "DCDC_PA_OUT_42") (pintype "power_in"))
    )
    (net (code "6") (name "DCDC_PA_SW_N") (class "Default")
      (node (ref "U2") (pin "41") (pinfunction "DCDC_PA_SW_N_41") (pintype "power_in"))
    )
    (net (code "7") (name "DCDC_PA_SW_P") (class "Default")
      (node (ref "U2") (pin "40") (pinfunction "DCDC_PA_SW_P_40") (pintype "power_in"))
    )
    (net (code "8") (name "DC_ANA2") (class "Default")
      (node (ref "JP2") (pin "1") (pinfunction "1_1") (pintype "passive"))
      (node (ref "U2") (pin "46") (pinfunction "DCDC_ANA2_SW_N_46") (pintype "bidirectional"))
    )
    (net (code "9") (name "DC_DIGSW") (class "Default")
      (node (ref "L3") (pin "2") (pinfunction "2_2") (pintype "passive"))
      (node (ref "U2") (pin "43") (pinfunction "DCDC_DIG_SW_43") (pintype "power_in"))
    )
    (net (code "10") (name "FLASH_P_ENN") (class "Default")
      (node (ref "HDR1") (pin "2") (pinfunction "2_2") (pintype "bidirectional"))
      (node (ref "U3") (pin "P51") (pinfunction "FLASH_P_ENN_P51") (pintype "bidirectional"))
    )
    (net (code "11") (name "FLS_SPI_CLK") (class "Default")
      (node (ref "IC2") (pin "6") (pinfunction "CLK_6") (pintype "bidirectional"))
      (node (ref "R6") (pin "1") (pinfunction "1_1") (pintype "passive"))
      (node (ref "U2") (pin "11") (pinfunction "FLASH_SPI_CLK_11") (pintype "output"))
    )
    (net (code "12") (name "FLS_SPI_CS") (class "Default")
      (node (ref "IC2") (pin "1") (pinfunction "~{CS}_1") (pintype "bidirectional"))
      (node (ref "R8") (pin "1") (pinfunction "1_1") (pintype "passive"))
      (node (ref "U2") (pin "14") (pinfunction "FLASH_SPI_CS_14") (pintype "output"))
    )
    (net (code "13") (name "FLS_SPI_DIN") (class "Default")
      (node (ref "IC2") (pin "2") (pinfunction "DO_(IO1)_2") (pintype "bidirectional"))
      (node (ref "U2") (pin "13") (pinfunction "FLASH_SPI_DIN_13") (pintype "input"))
    )
    (net (code "14") (name "FLS_SPI_DOUT") (class "Default")
      (node (ref "IC2") (pin "5") (pinfunction "DI_(IO0)_5") (pintype "bidirectional"))
      (node (ref "R7") (pin "1") (pinfunction "1_1") (pintype "passive"))
      (node (ref "U2") (pin "12") (pinfunction "FLASH_SPI_DOUT_12") (pintype "output"))
    )
    (net (code "15") (name "GND") (class "Default")
      (node (ref "BATT_1") (pin "-") (pinfunction "-_-") (pintype "passive"))
      (node (ref "BATT_2") (pin "1") (pinfunction "1_1") (pintype "bidirectional"))
      (node (ref "C1") (pin "2") (pinfunction "2_2") (pintype "passive"))
      (node (ref "C10") (pin "2") (pinfunction "2_2") (pintype "passive"))
      (node (ref "C11") (pin "2") (pinfunction "2_2") (pintype "passive"))
      (node (ref "C12") (pin "2") (pinfunction "2_2") (pintype "passive"))
      (node (ref "C13") (pin "2") (pinfunction "2_2") (pintype "passive"))
      (node (ref "C14") (pin "2") (pinfunction "2_2") (pintype "passive"))
      (node (ref "C15") (pin "2") (pinfunction "2_2") (pintype "passive"))
      (node (ref "C16") (pin "2") (pinfunction "2_2") (pintype "passive"))
      (node (ref "C17") (pin "2") (pinfunction "2_2") (pintype "passive"))
      (node (ref "C18") (pin "2") (pinfunction "2_2") (pintype "passive"))
      (node (ref "C19") (pin "2") (pinfunction "2_2") (pintype "passive"))
      (node (ref "C2") (pin "2") (pinfunction "2_2") (pintype "passive"))
      (node (ref "C20") (pin "2") (pinfunction "2_2") (pintype "passive"))
      (node (ref "C21") (pin "2") (pinfunction "2_2") (pintype "passive"))
      (node (ref "C22") (pin "2") (pinfunction "2_2") (pintype "passive"))
      (node (ref "C3") (pin "2") (pinfunction "2_2") (pintype "passive"))
      (node (ref "C4") (pin "2") (pinfunction "2_2") (pintype "passive"))
      (node (ref "C5") (pin "2") (pinfunction "2_2") (pintype "passive"))
      (node (ref "C6") (pin "2") (pinfunction "2_2") (pintype "passive"))
      (node (ref "C7") (pin "2") (pinfunction "2_2") (pintype "passive"))
      (node (ref "C8") (pin "-") (pinfunction "-_-") (pintype "passive"))
      (node (ref "C9") (pin "2") (pinfunction "2_2") (pintype "passive"))
      (node (ref "D1") (pin "2") (pinfunction "2_2") (pintype "bidirectional"))
      (node (ref "HDR1") (pin "8") (pinfunction "8_8") (pintype "bidirectional"))
      (node (ref "IC1") (pin "4") (pinfunction "PS/SYNC_4") (pintype "passive"))
      (node (ref "IC1") (pin "7") (pinfunction "GND_7") (pintype "passive"))
      (node (ref "IC1") (pin "PAD") (pinfunction "PGND_PAD") (pintype "passive"))
      (node (ref "IC2") (pin "4") (pinfunction "GND_4") (pintype "bidirectional"))
      (node (ref "LED1") (pin "1") (pinfunction "K_1") (pintype "bidirectional"))
      (node (ref "Q1") (pin "3") (pinfunction "S_3") (pintype "bidirectional"))
      (node (ref "Q2") (pin "3") (pinfunction "S_3") (pintype "bidirectional"))
      (node (ref "Q3") (pin "3") (pinfunction "S_3") (pintype "bidirectional"))
      (node (ref "Q4") (pin "3") (pinfunction "S_3") (pintype "bidirectional"))
      (node (ref "Q5") (pin "2") (pinfunction "S_2") (pintype "bidirectional"))
      (node (ref "R1") (pin "2") (pinfunction "2_2") (pintype "passive"))
      (node (ref "R11") (pin "2") (pinfunction "2_2") (pintype "passive"))
      (node (ref "R12") (pin "2") (pinfunction "2_2") (pintype "passive"))
      (node (ref "R13") (pin "1") (pinfunction "1_1") (pintype "passive"))
      (node (ref "R17") (pin "1") (pinfunction "1_1") (pintype "passive"))
      (node (ref "R19") (pin "1") (pinfunction "1_1") (pintype "passive"))
      (node (ref "R21") (pin "1") (pinfunction "1_1") (pintype "passive"))
      (node (ref "R23") (pin "1") (pinfunction "1_1") (pintype "passive"))
      (node (ref "R25") (pin "1") (pinfunction "1_1") (pintype "passive"))
      (node (ref "R4") (pin "1") (pinfunction "1_1") (pintype "passive"))
      (node (ref "R6") (pin "2") (pinfunction "2_2") (pintype "passive"))
      (node (ref "R7") (pin "2") (pinfunction "2_2") (pintype "passive"))
      (node (ref "R9") (pin "1") (pinfunction "1_1") (pintype "passive"))
      (node (ref "S1") (pin "2") (pinfunction "COM_2") (pintype "bidirectional"))
      (node (ref "U2") (pin "33") (pinfunction "VDD_PA_IN_33") (pintype "power_in"))
      (node (ref "U2") (pin "39") (pinfunction "VIN_DCDC_PA_39") (pintype "power_in"))
      (node (ref "U2") (pin "65") (pinfunction "GND_TAB_65") (pintype "power_in"))
      (node (ref "U2") (pin "V") (pinfunction "V0_V") (pintype "bidirectional"))
      (node (ref "U2") (pin "V_1") (pinfunction "V1_V_1") (pintype "bidirectional"))
      (node (ref "U2") (pin "V_10") (pinfunction "V10_V_10") (pintype "bidirectional"))
      (node (ref "U2") (pin "V_11") (pinfunction "V11_V_11") (pintype "bidirectional"))
      (node (ref "U2") (pin "V_12") (pinfunction "V12_V_12") (pintype "bidirectional"))
      (node (ref "U2") (pin "V_13") (pinfunction "V13_V_13") (pintype "bidirectional"))
      (node (ref "U2") (pin "V_14") (pinfunction "V14_V_14") (pintype "bidirectional"))
      (node (ref "U2") (pin "V_15") (pinfunction "V15_V_15") (pintype "bidirectional"))
      (node (ref "U2") (pin "V_16") (pinfunction "V16_V_16") (pintype "bidirectional"))
      (node (ref "U2") (pin "V_17") (pinfunction "V17_V_17") (pintype "bidirectional"))
      (node (ref "U2") (pin "V_18") (pinfunction "V18_V_18") (pintype "bidirectional"))
      (node (ref "U2") (pin "V_19") (pinfunction "V19_V_19") (pintype "bidirectional"))
      (node (ref "U2") (pin "V_2") (pinfunction "V2_V_2") (pintype "bidirectional"))
      (node (ref "U2") (pin "V_20") (pinfunction "V20_V_20") (pintype "bidirectional"))
      (node (ref "U2") (pin "V_21") (pinfunction "V21_V_21") (pintype "bidirectional"))
      (node (ref "U2") (pin "V_22") (pinfunction "V22_V_22") (pintype "bidirectional"))
      (node (ref "U2") (pin "V_23") (pinfunction "V23_V_23") (pintype "bidirectional"))
      (node (ref "U2") (pin "V_24") (pinfunction "V24_V_24") (pintype "bidirectional"))
      (node (ref "U2") (pin "V_25") (pinfunction "V25_V_25") (pintype "bidirectional"))
      (node (ref "U2") (pin "V_26") (pinfunction "V26_V_26") (pintype "bidirectional"))
      (node (ref "U2") (pin "V_27") (pinfunction "V27_V_27") (pintype "bidirectional"))
      (node (ref "U2") (pin "V_28") (pinfunction "V28_V_28") (pintype "bidirectional"))
      (node (ref "U2") (pin "V_29") (pinfunction "V29_V_29") (pintype "bidirectional"))
      (node (ref "U2") (pin "V_3") (pinfunction "V3_V_3") (pintype "bidirectional"))
      (node (ref "U2") (pin "V_30") (pinfunction "V30_V_30") (pintype "bidirectional"))
      (node (ref "U2") (pin "V_31") (pinfunction "V31_V_31") (pintype "bidirectional"))
      (node (ref "U2") (pin "V_32") (pinfunction "V32_V_32") (pintype "bidirectional"))
      (node (ref "U2") (pin "V_33") (pinfunction "V33_V_33") (pintype "bidirectional"))
      (node (ref "U2") (pin "V_34") (pinfunction "V34_V_34") (pintype "bidirectional"))
      (node (ref "U2") (pin "V_35") (pinfunction "V35_V_35") (pintype "bidirectional"))
      (node (ref "U2") (pin "V_36") (pinfunction "V36_V_36") (pintype "bidirectional"))
      (node (ref "U2") (pin "V_37") (pinfunction "V37_V_37") (pintype "bidirectional"))
      (node (ref "U2") (pin "V_38") (pinfunction "V38_V_38") (pintype "bidirectional"))
      (node (ref "U2") (pin "V_39") (pinfunction "V39_V_39") (pintype "bidirectional"))
      (node (ref "U2") (pin "V_4") (pinfunction "V4_V_4") (pintype "bidirectional"))
      (node (ref "U2") (pin "V_40") (pinfunction "V40_V_40") (pintype "bidirectional"))
      (node (ref "U2") (pin "V_41") (pinfunction "V41_V_41") (pintype "bidirectional"))
      (node (ref "U2") (pin "V_42") (pinfunction "V42_V_42") (pintype "bidirectional"))
      (node (ref "U2") (pin "V_43") (pinfunction "V43_V_43") (pintype "bidirectional"))
      (node (ref "U2") (pin "V_44") (pinfunction "V44_V_44") (pintype "bidirectional"))
      (node (ref "U2") (pin "V_45") (pinfunction "V45_V_45") (pintype "bidirectional"))
      (node (ref "U2") (pin "V_46") (pinfunction "V46_V_46") (pintype "bidirectional"))
      (node (ref "U2") (pin "V_47") (pinfunction "V47_V_47") (pintype "bidirectional"))
      (node (ref "U2") (pin "V_48") (pinfunction "V48_V_48") (pintype "bidirectional"))
      (node (ref "U2") (pin "V_5") (pinfunction "V5_V_5") (pintype "bidirectional"))
      (node (ref "U2") (pin "V_6") (pinfunction "V6_V_6") (pintype "bidirectional"))
      (node (ref "U2") (pin "V_7") (pinfunction "V7_V_7") (pintype "bidirectional"))
      (node (ref "U2") (pin "V_8") (pinfunction "V8_V_8") (pintype "bidirectional"))
      (node (ref "U2") (pin "V_9") (pinfunction "V9_V_9") (pintype "bidirectional"))
      (node (ref "U3") (pin "P1") (pinfunction "GND1_P1") (pintype "bidirectional"))
      (node (ref "U3") (pin "P10") (pinfunction "AI_0_P10") (pintype "bidirectional"))
      (node (ref "U3") (pin "P11") (pinfunction "GND2_P11") (pintype "bidirectional"))
      (node (ref "U3") (pin "P16") (pinfunction "TDI_P16") (pintype "bidirectional"))
      (node (ref "U3") (pin "P18") (pinfunction "TMS_P18") (pintype "bidirectional"))
      (node (ref "U3") (pin "P20") (pinfunction "GND3_P20") (pintype "bidirectional"))
      (node (ref "U3") (pin "P30") (pinfunction "GND4_P30") (pintype "bidirectional"))
      (node (ref "U3") (pin "P34") (pinfunction "GND5_P34") (pintype "bidirectional"))
      (node (ref "U3") (pin "P37") (pinfunction "GND6_P37") (pintype "bidirectional"))
      (node (ref "U3") (pin "P42") (pinfunction "GND7_P42") (pintype "bidirectional"))
      (node (ref "U3") (pin "P49") (pinfunction "SPIS_SCK/SCL_P49") (pintype "bidirectional"))
      (node (ref "U3") (pin "P56") (pinfunction "GND8_P56") (pintype "bidirectional"))
      (node (ref "U3") (pin "P57") (pinfunction "UART_RX_RTSN_P57") (pintype "bidirectional"))
      (node (ref "U3") (pin "P59") (pinfunction "UART_RX_P59") (pintype "bidirectional"))
      (node (ref "U3") (pin "P64") (pinfunction "RADIO_INHIBIT_P64") (pintype "bidirectional"))
      (node (ref "U3") (pin "P66") (pinfunction "GND9_P66") (pintype "bidirectional"))
      (node (ref "U3") (pin "P7") (pinfunction "AI_2_P7") (pintype "bidirectional"))
      (node (ref "U3") (pin "P8") (pinfunction "AI_1_P8") (pintype "bidirectional"))
      (node (ref "U3") (pin "P9") (pinfunction "AI_3_P9") (pintype "bidirectional"))
    )
    (net (code "16") (name "GPIO2") (class "Default")
      (node (ref "R18") (pin "1") (pinfunction "1_1") (pintype "passive"))
      (node (ref "R19") (pin "2") (pinfunction "2_2") (pintype "passive"))
      (node (ref "U2") (pin "57") (pinfunction "GPIO2_57") (pintype "bidirectional"))
    )
    (net (code "17") (name "GPIO3") (class "Default")
      (node (ref "R20") (pin "1") (pinfunction "1_1") (pintype "passive"))
      (node (ref "R21") (pin "2") (pinfunction "2_2") (pintype "passive"))
      (node (ref "U2") (pin "58") (pinfunction "GPIO3_58") (pintype "bidirectional"))
    )
    (net (code "18") (name "GPIO4") (class "Default")
      (node (ref "R24") (pin "2") (pinfunction "2_2") (pintype "passive"))
      (node (ref "R25") (pin "2") (pinfunction "2_2") (pintype "passive"))
      (node (ref "U2") (pin "59") (pinfunction "GPIO4_59") (pintype "bidirectional"))
    )
    (net (code "19") (name "GPIO5") (class "Default")
      (node (ref "R22") (pin "2") (pinfunction "2_2") (pintype "passive"))
      (node (ref "R23") (pin "2") (pinfunction "2_2") (pintype "passive"))
      (node (ref "U2") (pin "60") (pinfunction "GPIO5_60") (pintype "bidirectional"))
    )
    (net (code "20") (name "GPIO12") (class "Default")
      (node (ref "Q4") (pin "1") (pinfunction "G_1") (pintype "bidirectional"))
      (node (ref "U2") (pin "3") (pinfunction "GPIO12_3") (pintype "bidirectional"))
    )
    (net (code "21") (name "GPIO13") (class "Default")
      (node (ref "Q1") (pin "1") (pinfunction "G_1") (pintype "bidirectional"))
      (node (ref "U2") (pin "4") (pinfunction "GPIO13_4") (pintype "bidirectional"))
    )
    (net (code "22") (name "GPIO14") (class "Default")
      (node (ref "Q2") (pin "1") (pinfunction "G_1") (pintype "bidirectional"))
      (node (ref "U2") (pin "5") (pinfunction "GPIO14_5") (pintype "bidirectional"))
    )
    (net (code "23") (name "GPIO15") (class "Default")
      (node (ref "Q3") (pin "1") (pinfunction "G_1") (pintype "bidirectional"))
      (node (ref "U2") (pin "6") (pinfunction "GPIO15_6") (pintype "bidirectional"))
    )
    (net (code "24") (name "GPIO22") (class "Default")
      (node (ref "IC1") (pin "3") (pinfunction "EN_3") (pintype "passive"))
      (node (ref "U2") (pin "15") (pinfunction "GPIO22_15") (pintype "bidirectional"))
    )
    (net (code "25") (name "GPIO31") (class "Default")
      (node (ref "JP2") (pin "2") (pinfunction "2_2") (pintype "passive"))
    )
    (net (code "26") (name "IPCS_MISO") (class "Default")
      (node (ref "HDR1") (pin "5") (pinfunction "5_5") (pintype "bidirectional"))
      (node (ref "U3") (pin "P33") (pinfunction "IPCS_MISO_P33") (pintype "bidirectional"))
    )
    (net (code "27") (name "IPCS_MOSI") (class "Default")
      (node (ref "HDR1") (pin "4") (pinfunction "4_4") (pintype "bidirectional"))
      (node (ref "U3") (pin "P35") (pinfunction "IPCS_MOSI_P35") (pintype "bidirectional"))
    )
    (net (code "28") (name "IPCS_SCK") (class "Default")
      (node (ref "HDR1") (pin "3") (pinfunction "3_3") (pintype "bidirectional"))
      (node (ref "U3") (pin "P36") (pinfunction "IPCS_SCK_P36") (pintype "bidirectional"))
    )
    (net (code "29") (name "IPCS_SSN") (class "Default")
      (node (ref "HDR1") (pin "1") (pinfunction "1_1") (pintype "bidirectional"))
      (node (ref "U3") (pin "P39") (pinfunction "IPCS_SSN_P39") (pintype "bidirectional"))
    )
    (net (code "30") (name "Net-(AC1-GND_1)") (class "Default")
      (node (ref "AC1") (pin "2") (pinfunction "GND_1_2") (pintype "power_in"))
      (node (ref "AC1") (pin "4") (pinfunction "GND_2_4") (pintype "power_in"))
      (node (ref "AC1") (pin "5") (pinfunction "GND_3_5") (pintype "power_in"))
      (node (ref "Q1") (pin "2") (pinfunction "D_2") (pintype "bidirectional"))
      (node (ref "U6") (pin "P$3") (pinfunction "GND_P$3") (pintype "power_in"))
      (node (ref "X1") (pin "4") (pinfunction "4_4") (pintype "bidirectional"))
      (node (ref "X2") (pin "4") (pinfunction "4_4") (pintype "bidirectional"))
    )
    (net (code "31") (name "Net-(D2-A)") (class "Default")
      (node (ref "D2") (pin "2") (pinfunction "A_2") (pintype "bidirectional"))
      (node (ref "R16") (pin "1") (pinfunction "1_1") (pintype "passive"))
    )
    (net (code "32") (name "Net-(IC1-FB)") (class "Default")
      (node (ref "C7") (pin "1") (pinfunction "1_1") (pintype "passive"))
      (node (ref "IC1") (pin "8") (pinfunction "FB_8") (pintype "passive"))
      (node (ref "R4") (pin "2") (pinfunction "2_2") (pintype "passive"))
      (node (ref "R5") (pin "1") (pinfunction "1_1") (pintype "passive"))
    )
    (net (code "33") (name "Net-(IC1-L1)") (class "Default")
      (node (ref "IC1") (pin "1") (pinfunction "L1_1") (pintype "passive"))
      (node (ref "L1") (pin "2") (pinfunction "2_2") (pintype "passive"))
    )
    (net (code "34") (name "Net-(IC1-L2)") (class "Default")
      (node (ref "IC1") (pin "10") (pinfunction "L2_10") (pintype "passive"))
      (node (ref "L1") (pin "1") (pinfunction "1_1") (pintype "passive"))
    )
    (net (code "35") (name "Net-(IC1-PG)") (class "Default")
      (node (ref "IC1") (pin "5") (pinfunction "PG_5") (pintype "passive"))
      (node (ref "R3") (pin "1") (pinfunction "1_1") (pintype "passive"))
    )
    (net (code "36") (name "Net-(IC1-VAUX)") (class "Default")
      (node (ref "C6") (pin "1") (pinfunction "1_1") (pintype "passive"))
      (node (ref "IC1") (pin "6") (pinfunction "VAUX_6") (pintype "passive"))
    )
    (net (code "37") (name "Net-(JP1-Pad1)") (class "Default")
      (node (ref "JP1") (pin "1") (pinfunction "1_1") (pintype "passive"))
      (node (ref "JP1") (pin "3") (pinfunction "3_3") (pintype "passive"))
      (node (ref "JP1") (pin "5") (pinfunction "5_5") (pintype "passive"))
      (node (ref "R2") (pin "1") (pinfunction "1_1") (pintype "passive"))
    )
    (net (code "38") (name "Net-(LED1-A)") (class "Default")
      (node (ref "LED1") (pin "2") (pinfunction "A_2") (pintype "bidirectional"))
      (node (ref "R10") (pin "2") (pinfunction "2_2") (pintype "passive"))
    )
    (net (code "39") (name "Net-(PB2-Pad2)") (class "Default")
      (node (ref "PB2") (pin "2") (pinfunction "2_2") (pintype "bidirectional"))
      (node (ref "R17") (pin "2") (pinfunction "2_2") (pintype "passive"))
    )
    (net (code "40") (name "Net-(Q2-D)") (class "Default")
      (node (ref "Q2") (pin "2") (pinfunction "D_2") (pintype "bidirectional"))
      (node (ref "U4") (pin "P$2") (pinfunction "GND_P$2") (pintype "power_in"))
    )
    (net (code "41") (name "Net-(Q3-D)") (class "Default")
      (node (ref "Q3") (pin "2") (pinfunction "D_2") (pintype "bidirectional"))
      (node (ref "U5") (pin "P$3") (pinfunction "GND_P$3") (pintype "power_in"))
    )
    (net (code "42") (name "Net-(Q4-D)") (class "Default")
      (node (ref "Q4") (pin "2") (pinfunction "D_2") (pintype "bidirectional"))
      (node (ref "X3") (pin "4") (pinfunction "4_4") (pintype "bidirectional"))
    )
    (net (code "43") (name "Net-(U2-DCDC_ANA_SW)") (class "Default")
      (node (ref "L2") (pin "2") (pinfunction "2_2") (pintype "passive"))
      (node (ref "U2") (pin "38") (pinfunction "DCDC_ANA_SW_38") (pintype "power_in"))
    )
    (net (code "44") (name "Net-(U2-RTC_XTAL_N)") (class "Default")
      (node (ref "C10") (pin "1") (pinfunction "1_1") (pintype "passive"))
      (node (ref "U2") (pin "52") (pinfunction "RTC_XTAL_N_52") (pintype "passive"))
      (node (ref "Y1") (pin "1") (pinfunction "1_1") (pintype "passive"))
    )
    (net (code "45") (name "Net-(U2-RTC_XTAL_P)") (class "Default")
      (node (ref "C11") (pin "1") (pinfunction "1_1") (pintype "passive"))
      (node (ref "U2") (pin "51") (pinfunction "RTC_XTAL_P_51") (pintype "passive"))
      (node (ref "Y1") (pin "3") (pinfunction "2_3") (pintype "passive"))
    )
    (net (code "46") (name "Net-(U2-VDD_PLL)") (class "Default")
      (node (ref "C5") (pin "1") (pinfunction "1_1") (pintype "passive"))
      (node (ref "U2") (pin "24") (pinfunction "VDD_PLL_24") (pintype "power_in"))
    )
    (net (code "47") (name "Net-(U2-VDD_RAM)") (class "Default")
      (node (ref "C4") (pin "1") (pinfunction "1_1") (pintype "passive"))
      (node (ref "U2") (pin "49") (pinfunction "VDD_RAM_49") (pintype "power_in"))
    )
    (net (code "48") (name "Net-(U4-RV)") (class "Default")
      (node (ref "R20") (pin "2") (pinfunction "2_2") (pintype "passive"))
      (node (ref "U4") (pin "P$3") (pinfunction "RV_P$3") (pintype "bidirectional"))
    )
    (net (code "49") (name "Net-(U4-TMP)") (class "Default")
      (node (ref "R18") (pin "2") (pinfunction "2_2") (pintype "passive"))
      (node (ref "U4") (pin "P$4") (pinfunction "TMP_P$4") (pintype "bidirectional"))
    )
    (net (code "50") (name "Net-(U5-SIG)") (class "Default")
      (node (ref "R24") (pin "1") (pinfunction "1_1") (pintype "passive"))
      (node (ref "U5") (pin "P$2") (pinfunction "SIG_P$2") (pintype "bidirectional"))
    )
    (net (code "51") (name "Net-(U6-SIG)") (class "Default")
      (node (ref "R22") (pin "1") (pinfunction "1_1") (pintype "passive"))
      (node (ref "U6") (pin "P$2") (pinfunction "SIG_P$2") (pintype "bidirectional"))
    )
    (net (code "52") (name "RESETN") (class "Default")
      (node (ref "HDR1") (pin "6") (pinfunction "6_6") (pintype "bidirectional"))
      (node (ref "Q5") (pin "3") (pinfunction "D_3") (pintype "bidirectional"))
      (node (ref "U3") (pin "P15") (pinfunction "RESETN_P15") (pintype "bidirectional"))
    )
    (net (code "53") (name "RST_BTN") (class "Default")
      (node (ref "C13") (pin "1") (pinfunction "1_1") (pintype "passive"))
      (node (ref "PB1") (pin "1") (pinfunction "1_1") (pintype "bidirectional"))
      (node (ref "Q5") (pin "1") (pinfunction "G_1") (pintype "bidirectional"))
      (node (ref "R9") (pin "2") (pinfunction "2_2") (pintype "passive"))
    )
    (net (code "54") (name "SCL") (class "Default")
      (node (ref "AC1") (pin "14") (pinfunction "SCL/SCLK_14") (pintype "input"))
      (node (ref "R14") (pin "2") (pinfunction "2_2") (pintype "passive"))
      (node (ref "U2") (pin "1") (pinfunction "GPIO10_1") (pintype "bidirectional"))
      (node (ref "X1") (pin "2") (pinfunction "2_2") (pintype "power_in"))
      (node (ref "X2") (pin "2") (pinfunction "2_2") (pintype "power_in"))
      (node (ref "X3") (pin "2") (pinfunction "2_2") (pintype "power_in"))
    )
    (net (code "55") (name "SDA") (class "Default")
      (node (ref "AC1") (pin "13") (pinfunction "SDA/SDI/SDIO_13") (pintype "bidirectional"))
      (node (ref "R15") (pin "2") (pinfunction "2_2") (pintype "passive"))
      (node (ref "U2") (pin "2") (pinfunction "GPIO11_2") (pintype "bidirectional"))
      (node (ref "X1") (pin "3") (pinfunction "3_3") (pintype "bidirectional"))
      (node (ref "X2") (pin "3") (pinfunction "3_3") (pintype "bidirectional"))
      (node (ref "X3") (pin "3") (pinfunction "3_3") (pintype "bidirectional"))
    )
    (net (code "56") (name "SOP0") (class "Default")
      (node (ref "JP1") (pin "6") (pinfunction "6_6") (pintype "passive"))
      (node (ref "R12") (pin "1") (pinfunction "1_1") (pintype "passive"))
      (node (ref "U2") (pin "35") (pinfunction "SOP0_35") (pintype "input"))
    )
    (net (code "57") (name "SOP1") (class "Default")
      (node (ref "JP1") (pin "4") (pinfunction "4_4") (pintype "passive"))
      (node (ref "R11") (pin "1") (pinfunction "1_1") (pintype "passive"))
      (node (ref "U2") (pin "34") (pinfunction "SOP1_34") (pintype "input"))
    )
    (net (code "58") (name "SOP2") (class "Default")
      (node (ref "JP1") (pin "2") (pinfunction "2_2") (pintype "passive"))
      (node (ref "R13") (pin "2") (pinfunction "2_2") (pintype "passive"))
      (node (ref "U2") (pin "21") (pinfunction "SOP2_21") (pintype "output"))
    )
    (net (code "59") (name "TCK") (class "Default")
      (node (ref "CN1") (pin "4") (pinfunction "4_4") (pintype "bidirectional"))
      (node (ref "R1") (pin "1") (pinfunction "1_1") (pintype "passive"))
      (node (ref "U2") (pin "19") (pinfunction "TCK_19") (pintype "bidirectional"))
    )
    (net (code "60") (name "TDI") (class "Default")
      (node (ref "CN1") (pin "2") (pinfunction "2_2") (pintype "bidirectional"))
      (node (ref "U2") (pin "16") (pinfunction "TDI_16") (pintype "bidirectional"))
    )
    (net (code "61") (name "TDO") (class "Default")
      (node (ref "CN1") (pin "1") (pinfunction "1_1") (pintype "bidirectional"))
      (node (ref "U2") (pin "17") (pinfunction "TDO_17") (pintype "bidirectional"))
    )
    (net (code "62") (name "TMS") (class "Default")
      (node (ref "CN1") (pin "3") (pinfunction "3_3") (pintype "bidirectional"))
      (node (ref "U2") (pin "20") (pinfunction "TMS_20") (pintype "bidirectional"))
    )
    (net (code "63") (name "UARTC0_RX") (class "Default")
      (node (ref "HDR1") (pin "10") (pinfunction "10_10") (pintype "bidirectional"))
      (node (ref "U2") (pin "8") (pinfunction "GPIO17_8") (pintype "bidirectional"))
      (node (ref "U3") (pin "P32") (pinfunction "UARTC0_RX_P32") (pintype "bidirectional"))
    )
    (net (code "64") (name "UARTC0_TX") (class "Default")
      (node (ref "HDR1") (pin "9") (pinfunction "9_9") (pintype "bidirectional"))
      (node (ref "U2") (pin "7") (pinfunction "GPIO16_7") (pintype "bidirectional"))
      (node (ref "U3") (pin "P31") (pinfunction "UARTC0_TX_P31") (pintype "bidirectional"))
    )
    (net (code "65") (name "VCC_DCDC") (class "Default")
      (node (ref "JP3") (pin "2") (pinfunction "2_2") (pintype "passive"))
    )
    (net (code "66") (name "VDD_ANA1") (class "Default")
      (node (ref "C19") (pin "1") (pinfunction "1_1") (pintype "passive"))
      (node (ref "C20") (pin "1") (pinfunction "1_1") (pintype "passive"))
      (node (ref "C21") (pin "1") (pinfunction "1_1") (pintype "passive"))
      (node (ref "C22") (pin "1") (pinfunction "1_1") (pintype "passive"))
      (node (ref "L2") (pin "1") (pinfunction "1_1") (pintype "passive"))
      (node (ref "U2") (pin "25") (pinfunction "LDO_IN2_25") (pintype "power_in"))
      (node (ref "U2") (pin "36") (pinfunction "LDO_IN1_36") (pintype "power_in"))
      (node (ref "U2") (pin "48") (pinfunction "VDD_ANA1_48") (pintype "power_in"))
    )
    (net (code "67") (name "VDD_ANA2") (class "Default")
      (node (ref "JP3") (pin "1") (pinfunction "1_1") (pintype "passive"))
      (node (ref "U2") (pin "47") (pinfunction "VDD_ANA2_47") (pintype "power_in"))
    )
    (net (code "68") (name "VDD_DIG") (class "Default")
      (node (ref "C16") (pin "1") (pinfunction "1_1") (pintype "passive"))
      (node (ref "C17") (pin "1") (pinfunction "1_1") (pintype "passive"))
      (node (ref "C18") (pin "1") (pinfunction "1_1") (pintype "passive"))
      (node (ref "L3") (pin "1") (pinfunction "1_1") (pintype "passive"))
      (node (ref "U2") (pin "56") (pinfunction "VDD_DIG2_56") (pintype "power_in"))
      (node (ref "U2") (pin "9") (pinfunction "VDD_DIG1_9") (pintype "power_in"))
    )
    (net (code "69") (name "unconnected-(AC1-INT1-Pad8)") (class "Default")
      (node (ref "AC1") (pin "8") (pinfunction "INT1_8") (pintype "input"))
    )
    (net (code "70") (name "unconnected-(AC1-INT2-Pad9)") (class "Default")
      (node (ref "AC1") (pin "9") (pinfunction "INT2_9") (pintype "input"))
    )
    (net (code "71") (name "unconnected-(AC1-NC-Pad10)") (class "Default")
      (node (ref "AC1") (pin "10") (pinfunction "NC_10") (pintype "no_connect"))
    )
    (net (code "72") (name "unconnected-(AC1-RESERVED_1-Pad3)") (class "Default")
      (node (ref "AC1") (pin "3") (pinfunction "RESERVED_1_3") (pintype "bidirectional"))
    )
    (net (code "73") (name "unconnected-(AC1-RESERVED_2-Pad11)") (class "Default")
      (node (ref "AC1") (pin "11") (pinfunction "RESERVED_2_11") (pintype "bidirectional"))
    )
    (net (code "74") (name "unconnected-(AC1-SDO{slash}ALT_ADDRESS-Pad12)") (class "Default")
      (node (ref "AC1") (pin "12") (pinfunction "SDO/ALT_ADDRESS_12") (pintype "bidirectional"))
    )
    (net (code "75") (name "unconnected-(AC1-VS-Pad6)") (class "Default")
      (node (ref "AC1") (pin "6") (pinfunction "VS_6") (pintype "bidirectional"))
    )
    (net (code "76") (name "unconnected-(D1-NC-Pad3)") (class "Default")
      (node (ref "D1") (pin "3") (pinfunction "NC_3") (pintype "no_connect"))
    )
    (net (code "77") (name "unconnected-(S1-NC-Pad3)") (class "Default")
      (node (ref "S1") (pin "3") (pinfunction "NC_3") (pintype "no_connect"))
    )
    (net (code "78") (name "unconnected-(S1-PadMH1)") (class "Default")
      (node (ref "S1") (pin "MH1") (pinfunction "MH1_MH1") (pintype "bidirectional"))
    )
    (net (code "79") (name "unconnected-(S1-PadMH2)") (class "Default")
      (node (ref "S1") (pin "MH2") (pinfunction "MH2_MH2") (pintype "bidirectional"))
    )
    (net (code "80") (name "unconnected-(S1-PadMH3)") (class "Default")
      (node (ref "S1") (pin "MH3") (pinfunction "MH3_MH3") (pintype "bidirectional"))
    )
    (net (code "81") (name "unconnected-(S1-PadMH4)") (class "Default")
      (node (ref "S1") (pin "MH4") (pinfunction "MH4_MH4") (pintype "bidirectional"))
    )
    (net (code "82") (name "unconnected-(U2-ANTSEL1-Pad29)") (class "Default")
      (node (ref "U2") (pin "29") (pinfunction "ANTSEL1_29") (pintype "output"))
    )
    (net (code "83") (name "unconnected-(U2-ANTSEL2-Pad30)") (class "Default")
      (node (ref "U2") (pin "30") (pinfunction "ANTSEL2_30") (pintype "output"))
    )
    (net (code "84") (name "unconnected-(U2-DCDC_ANA2_SW_P-Pad45)") (class "Default")
      (node (ref "U2") (pin "45") (pinfunction "DCDC_ANA2_SW_P_45") (pintype "bidirectional"))
    )
    (net (code "85") (name "unconnected-(U2-GPIO0-Pad50)") (class "Default")
      (node (ref "U2") (pin "50") (pinfunction "GPIO0_50") (pintype "bidirectional"))
    )
    (net (code "86") (name "unconnected-(U2-GPIO1-Pad55)") (class "Default")
      (node (ref "U2") (pin "55") (pinfunction "GPIO1_55") (pintype "bidirectional"))
    )
    (net (code "87") (name "unconnected-(U2-GPIO6-Pad61)") (class "Default")
      (node (ref "U2") (pin "61") (pinfunction "GPIO6_61") (pintype "bidirectional"))
    )
    (net (code "88") (name "unconnected-(U2-GPIO7-Pad62)") (class "Default")
      (node (ref "U2") (pin "62") (pinfunction "GPIO7_62") (pintype "bidirectional"))
    )
    (net (code "89") (name "unconnected-(U2-GPIO8-Pad63)") (class "Default")
      (node (ref "U2") (pin "63") (pinfunction "GPIO8_63") (pintype "bidirectional"))
    )
    (net (code "90") (name "unconnected-(U2-GPIO9-Pad64)") (class "Default")
      (node (ref "U2") (pin "64") (pinfunction "GPIO9_64") (pintype "bidirectional"))
    )
    (net (code "91") (name "unconnected-(U2-GPIO28-Pad18)") (class "Default")
      (node (ref "U2") (pin "18") (pinfunction "GPIO28_18") (pintype "bidirectional"))
    )
    (net (code "92") (name "unconnected-(U2-GPIO30-Pad53)") (class "Default")
      (node (ref "U2") (pin "53") (pinfunction "GPIO30_53") (pintype "bidirectional"))
    )
    (net (code "93") (name "unconnected-(U2-NC-Pad28)") (class "Default")
      (node (ref "U2") (pin "28") (pinfunction "NC_28") (pintype "passive"))
    )
    (net (code "94") (name "unconnected-(U2-NC_2-Pad26)") (class "Default")
      (node (ref "U2") (pin "26") (pinfunction "NC_2_26") (pintype "passive"))
    )
    (net (code "95") (name "unconnected-(U2-NC_3-Pad27)") (class "Default")
      (node (ref "U2") (pin "27") (pinfunction "NC_3_27") (pintype "passive"))
    )
    (net (code "96") (name "unconnected-(U2-RF_BG-Pad31)") (class "Default")
      (node (ref "U2") (pin "31") (pinfunction "RF_BG_31") (pintype "passive"))
    )
    (net (code "97") (name "unconnected-(U2-WLAN_XTAL_N-Pad22)") (class "Default")
      (node (ref "U2") (pin "22") (pinfunction "WLAN_XTAL_N_22") (pintype "passive"))
    )
    (net (code "98") (name "unconnected-(U2-WLAN_XTAL_P-Pad23)") (class "Default")
      (node (ref "U2") (pin "23") (pinfunction "WLAN_XTAL_P_23") (pintype "passive"))
    )
    (net (code "99") (name "unconnected-(U3-GPIO17-PadP4)") (class "Default")
      (node (ref "U3") (pin "P4") (pinfunction "GPIO17_P4") (pintype "bidirectional"))
    )
    (net (code "100") (name "unconnected-(U3-GPIO18-PadP5)") (class "Default")
      (node (ref "U3") (pin "P5") (pinfunction "GPIO18_P5") (pintype "bidirectional"))
    )
    (net (code "101") (name "unconnected-(U3-GPIO19-PadP6)") (class "Default")
      (node (ref "U3") (pin "P6") (pinfunction "GPIO19_P6") (pintype "bidirectional"))
    )
    (net (code "102") (name "unconnected-(U3-GPIO23-PadP21)") (class "Default")
      (node (ref "U3") (pin "P21") (pinfunction "GPIO23_P21") (pintype "bidirectional"))
    )
    (net (code "103") (name "unconnected-(U3-LPTIMER_EXT-PadP26)") (class "Default")
      (node (ref "U3") (pin "P26") (pinfunction "LPTIMER_EXT_P26") (pintype "bidirectional"))
    )
    (net (code "104") (name "unconnected-(U3-NC1-PadP3)") (class "Default")
      (node (ref "U3") (pin "P3") (pinfunction "NC1_P3") (pintype "bidirectional"))
    )
    (net (code "105") (name "unconnected-(U3-NC2-PadP13)") (class "Default")
      (node (ref "U3") (pin "P13") (pinfunction "NC2_P13") (pintype "bidirectional"))
    )
    (net (code "106") (name "unconnected-(U3-NC3-PadP14)") (class "Default")
      (node (ref "U3") (pin "P14") (pinfunction "NC3_P14") (pintype "bidirectional"))
    )
    (net (code "107") (name "unconnected-(U3-NC4-PadP29)") (class "Default")
      (node (ref "U3") (pin "P29") (pinfunction "NC4_P29") (pintype "bidirectional"))
    )
    (net (code "108") (name "unconnected-(U3-NC5-PadP52)") (class "Default")
      (node (ref "U3") (pin "P52") (pinfunction "NC5_P52") (pintype "bidirectional"))
    )
    (net (code "109") (name "unconnected-(U3-NC6-PadP53)") (class "Default")
      (node (ref "U3") (pin "P53") (pinfunction "NC6_P53") (pintype "bidirectional"))
    )
    (net (code "110") (name "unconnected-(U3-NC7-PadP65)") (class "Default")
      (node (ref "U3") (pin "P65") (pinfunction "NC7_P65") (pintype "bidirectional"))
    )
    (net (code "111") (name "unconnected-(U3-P$2-PadP2)") (class "Default")
      (node (ref "U3") (pin "P2") (pinfunction "P$2_P2") (pintype "bidirectional"))
    )
    (net (code "112") (name "unconnected-(U3-P$12-PadP12)") (class "Default")
      (node (ref "U3") (pin "P12") (pinfunction "P$12_P12") (pintype "bidirectional"))
    )
    (net (code "113") (name "unconnected-(U3-P$22-PadP22)") (class "Default")
      (node (ref "U3") (pin "P22") (pinfunction "P$22_P22") (pintype "bidirectional"))
    )
    (net (code "114") (name "unconnected-(U3-P$23-PadP23)") (class "Default")
      (node (ref "U3") (pin "P23") (pinfunction "P$23_P23") (pintype "bidirectional"))
    )
    (net (code "115") (name "unconnected-(U3-P$24-PadP24)") (class "Default")
      (node (ref "U3") (pin "P24") (pinfunction "P$24_P24") (pintype "bidirectional"))
    )
    (net (code "116") (name "unconnected-(U3-P$54-PadP54)") (class "Default")
      (node (ref "U3") (pin "P54") (pinfunction "P$54_P54") (pintype "bidirectional"))
    )
    (net (code "117") (name "unconnected-(U3-PWM0{slash}TIMER16_OUT-PadP46)") (class "Default")
      (node (ref "U3") (pin "P46") (pinfunction "PWM0/TIMER16_OUT_P46") (pintype "bidirectional"))
    )
    (net (code "118") (name "unconnected-(U3-SPIM_MISO-PadP38)") (class "Default")
      (node (ref "U3") (pin "P38") (pinfunction "SPIM_MISO_P38") (pintype "bidirectional"))
    )
    (net (code "119") (name "unconnected-(U3-SPIM_MOSI-PadP40)") (class "Default")
      (node (ref "U3") (pin "P40") (pinfunction "SPIM_MOSI_P40") (pintype "bidirectional"))
    )
    (net (code "120") (name "unconnected-(U3-SPIM_SCK-PadP41)") (class "Default")
      (node (ref "U3") (pin "P41") (pinfunction "SPIM_SCK_P41") (pintype "bidirectional"))
    )
    (net (code "121") (name "unconnected-(U3-SPIM_SS_0N-PadP44)") (class "Default")
      (node (ref "U3") (pin "P44") (pinfunction "SPIM_SS_0N_P44") (pintype "bidirectional"))
    )
    (net (code "122") (name "unconnected-(U3-SPIM_SS_1N-PadP43)") (class "Default")
      (node (ref "U3") (pin "P43") (pinfunction "SPIM_SS_1N_P43") (pintype "bidirectional"))
    )
    (net (code "123") (name "unconnected-(U3-SPIM_SS_2N-PadP28)") (class "Default")
      (node (ref "U3") (pin "P28") (pinfunction "SPIM_SS_2N_P28") (pintype "bidirectional"))
    )
    (net (code "124") (name "unconnected-(U3-SPIS_MISO{slash}UARTC1_TX-PadP47)") (class "Default")
      (node (ref "U3") (pin "P47") (pinfunction "SPIS_MISO/UARTC1_TX_P47") (pintype "bidirectional"))
    )
    (net (code "125") (name "unconnected-(U3-SPIS_MOSI_UARTC1_RX-PadP48)") (class "Default")
      (node (ref "U3") (pin "P48") (pinfunction "SPIS_MOSI_UARTC1_RX_P48") (pintype "bidirectional"))
    )
    (net (code "126") (name "unconnected-(U3-SPIS_SSN{slash}SDA-PadP50)") (class "Default")
      (node (ref "U3") (pin "P50") (pinfunction "SPIS_SSN/SDA_P50") (pintype "bidirectional"))
    )
    (net (code "127") (name "unconnected-(U3-TDO-PadP17)") (class "Default")
      (node (ref "U3") (pin "P17") (pinfunction "TDO_P17") (pintype "bidirectional"))
    )
    (net (code "128") (name "unconnected-(U3-TIMER8_EXT-PadP25)") (class "Default")
      (node (ref "U3") (pin "P25") (pinfunction "TIMER8_EXT_P25") (pintype "bidirectional"))
    )
    (net (code "129") (name "unconnected-(U3-TIMER16_EXT-PadP45)") (class "Default")
      (node (ref "U3") (pin "P45") (pinfunction "TIMER16_EXT_P45") (pintype "bidirectional"))
    )
    (net (code "130") (name "unconnected-(U3-UART_RX_CTSN-PadP58)") (class "Default")
      (node (ref "U3") (pin "P58") (pinfunction "UART_RX_CTSN_P58") (pintype "bidirectional"))
    )
    (net (code "131") (name "unconnected-(U3-UART_TX-PadP62)") (class "Default")
      (node (ref "U3") (pin "P62") (pinfunction "UART_TX_P62") (pintype "bidirectional"))
    )
    (net (code "132") (name "unconnected-(U3-UART_TX_CTSN-PadP61)") (class "Default")
      (node (ref "U3") (pin "P61") (pinfunction "UART_TX_CTSN_P61") (pintype "bidirectional"))
    )
    (net (code "133") (name "unconnected-(U3-UART_TX_RTSN-PadP60)") (class "Default")
      (node (ref "U3") (pin "P60") (pinfunction "UART_TX_RTSN_P60") (pintype "bidirectional"))
    )
  )
)
